# Alaska_1-1.net
KiCad netlist of a schematic drawn in Altium Designer
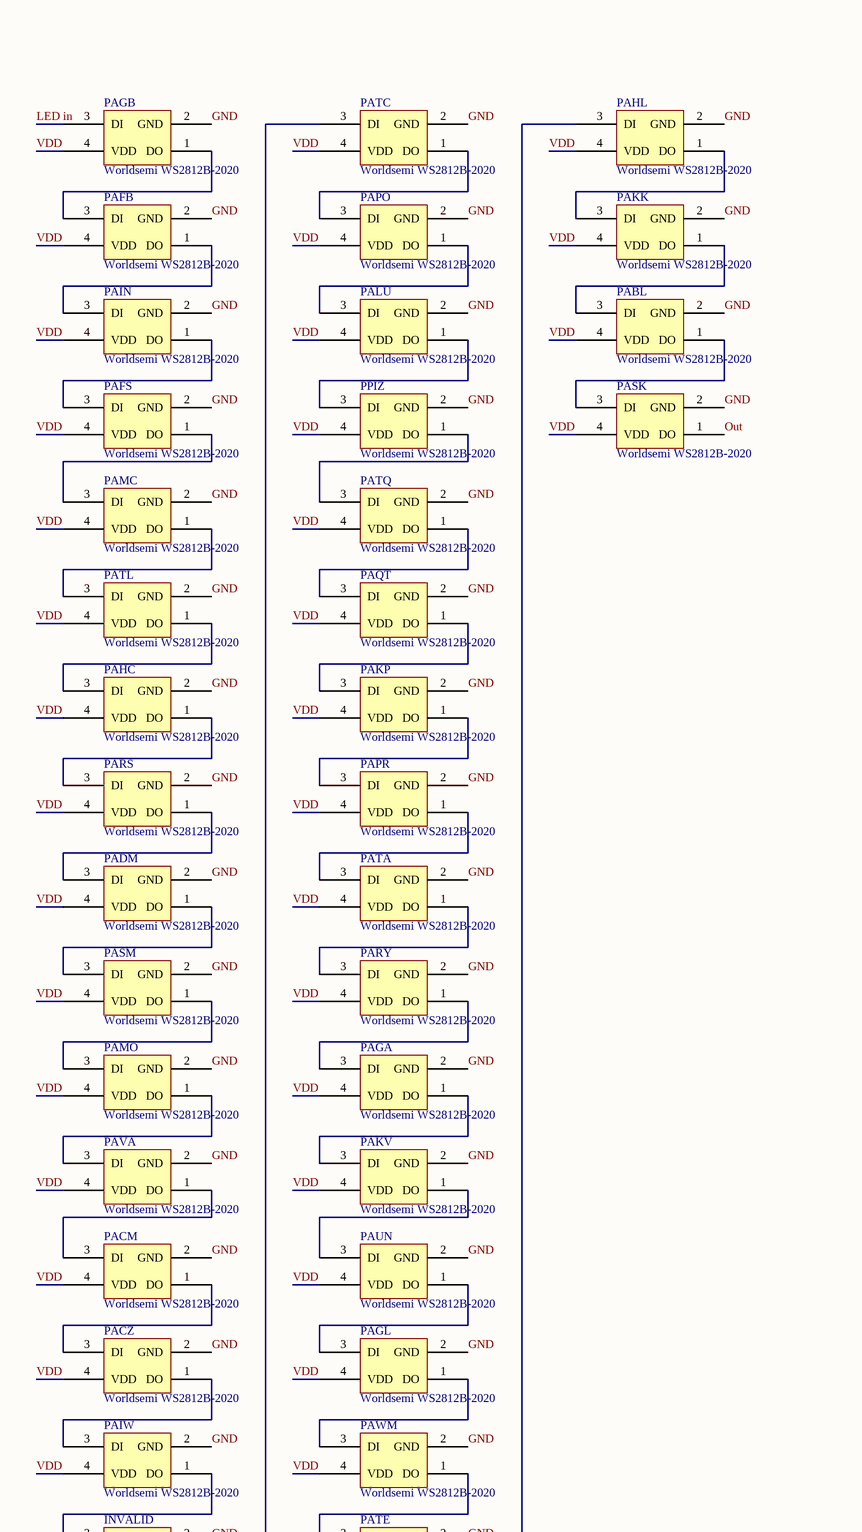
[diagram p0: Alaska 1-1.SchDoc, top left]
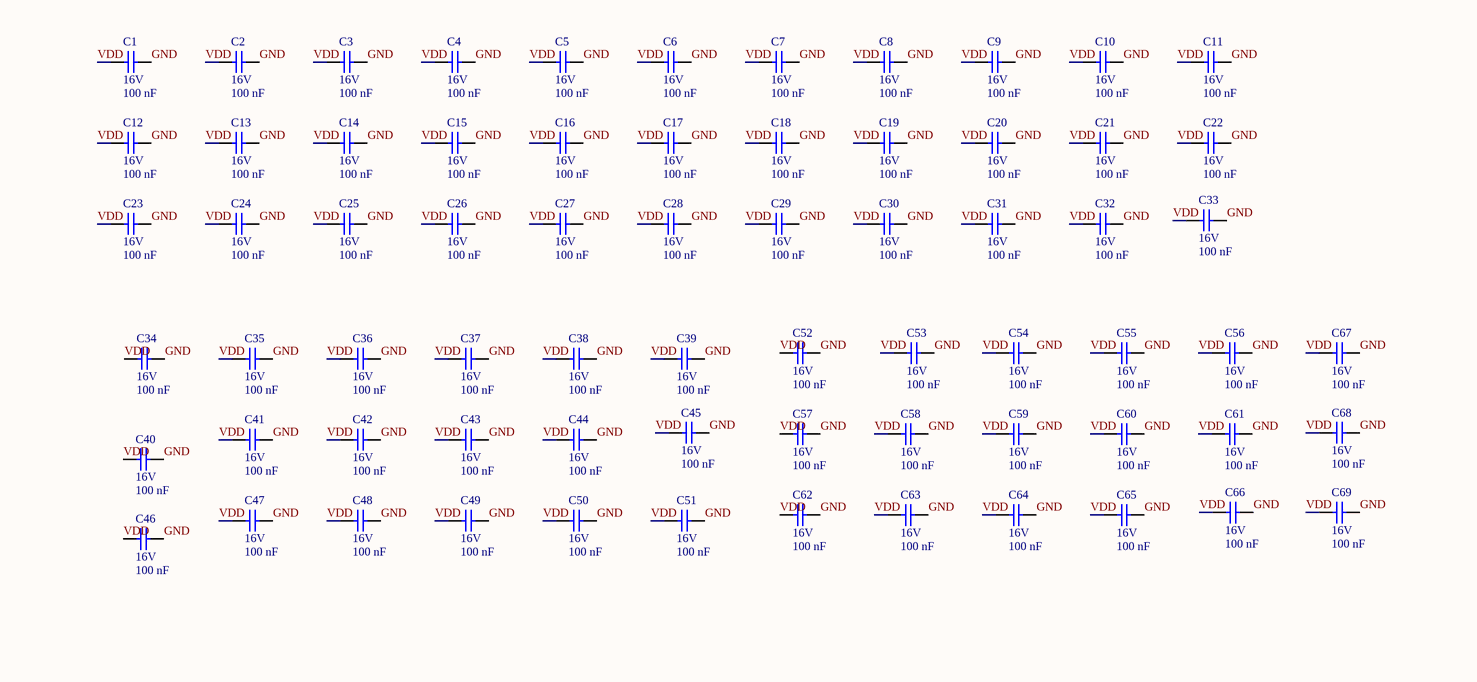
[diagram p1: Alaska 1-1.SchDoc, top middle]
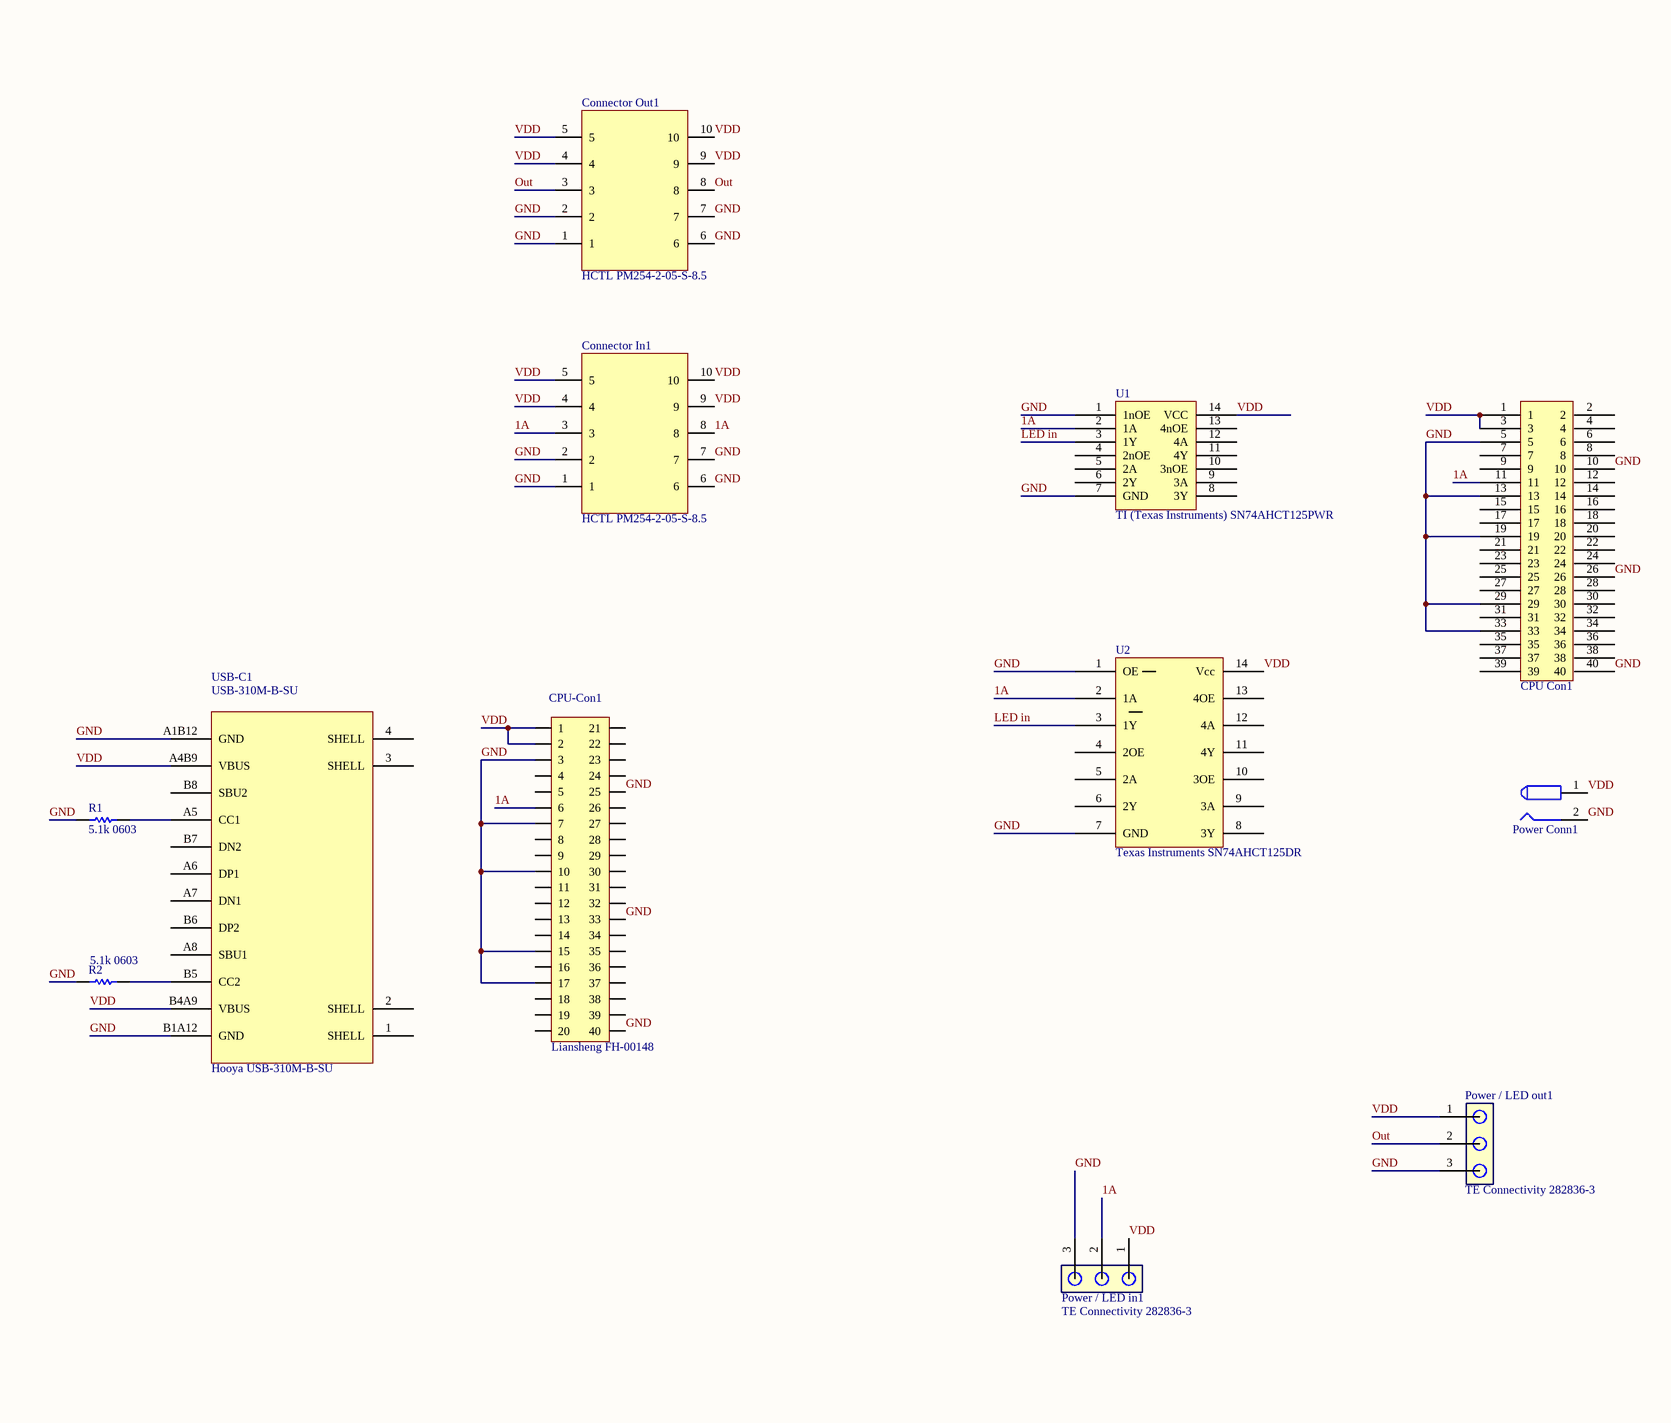
[diagram p2: Alaska 1-1.SchDoc, top right]
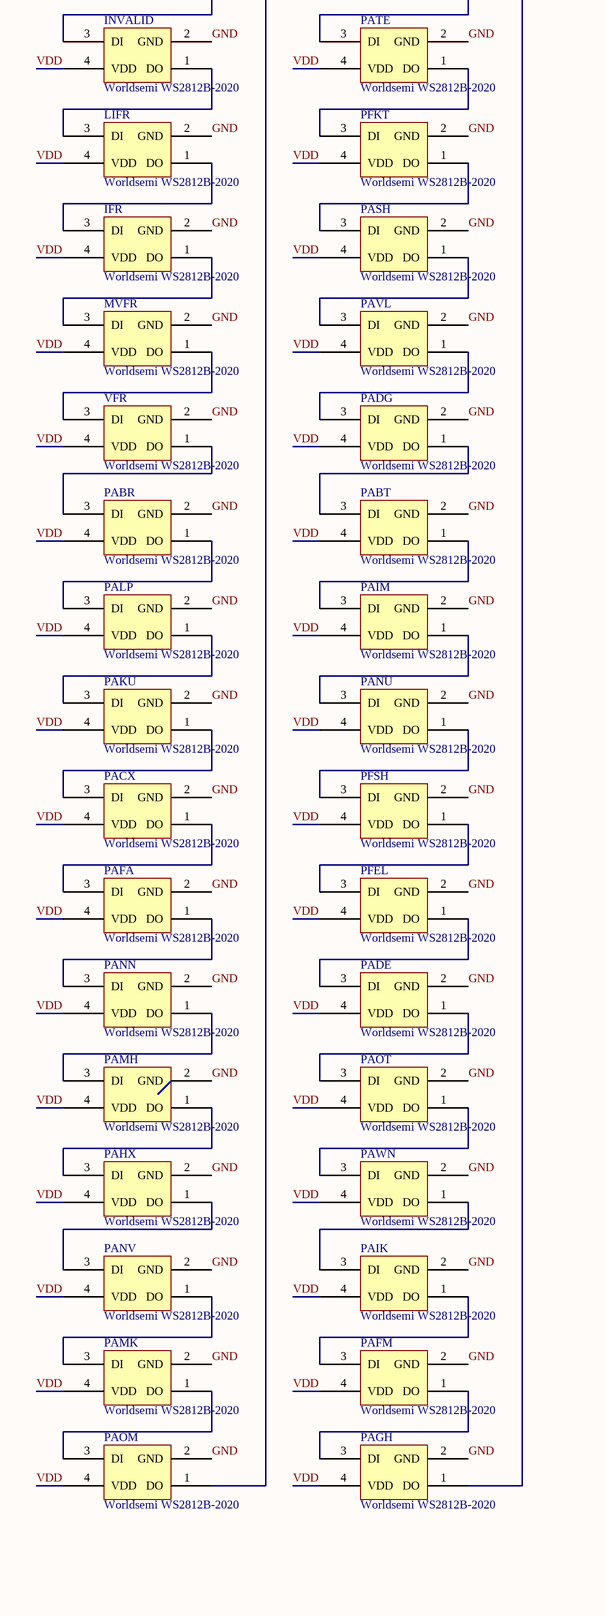
[diagram p3: Alaska 1-1.SchDoc, bottom left]
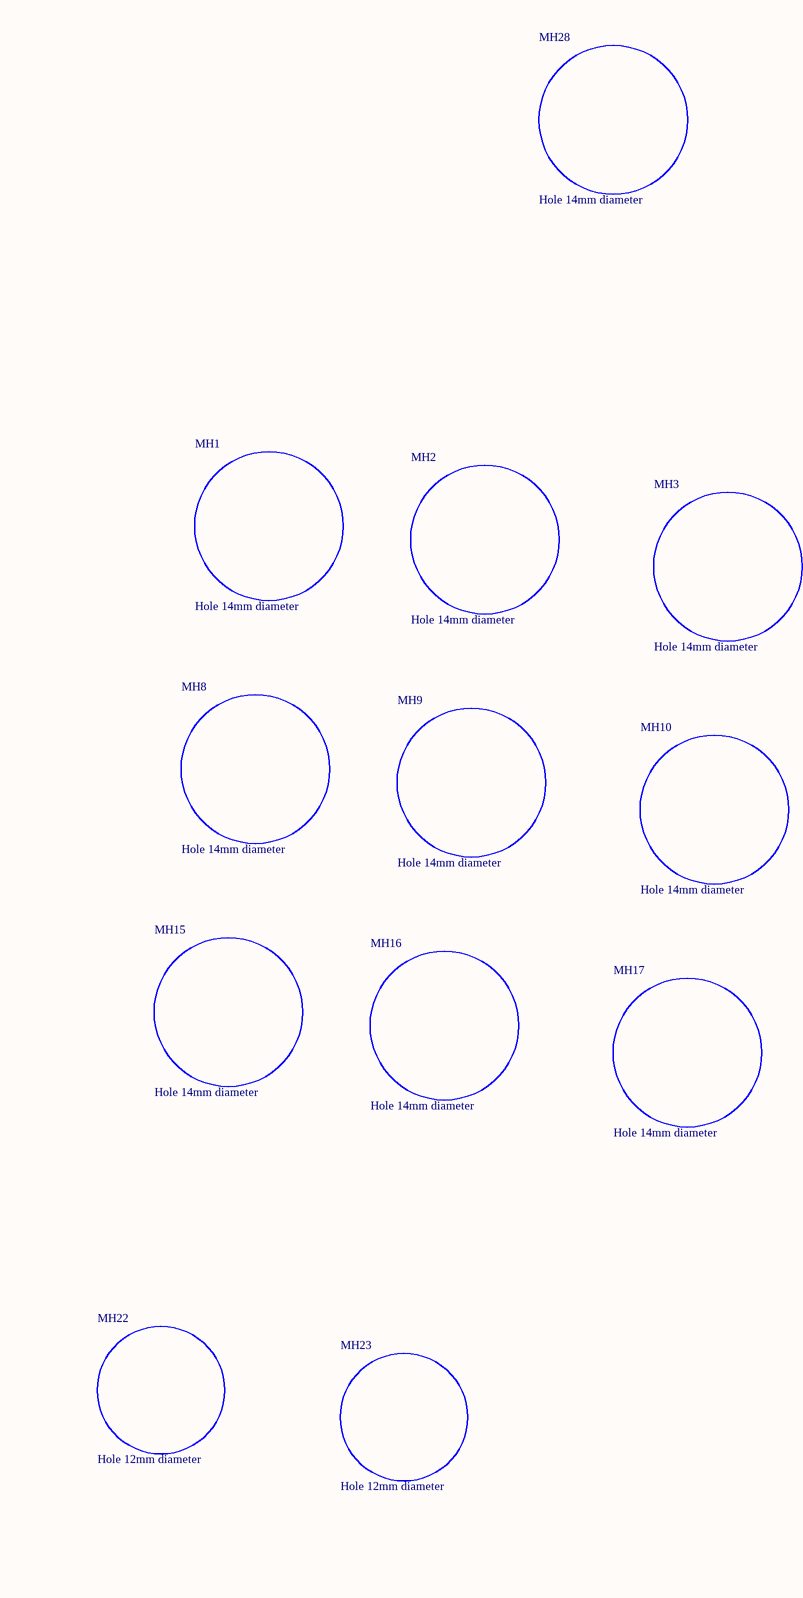
[diagram p4: Alaska 1-1.SchDoc, bottom middle]
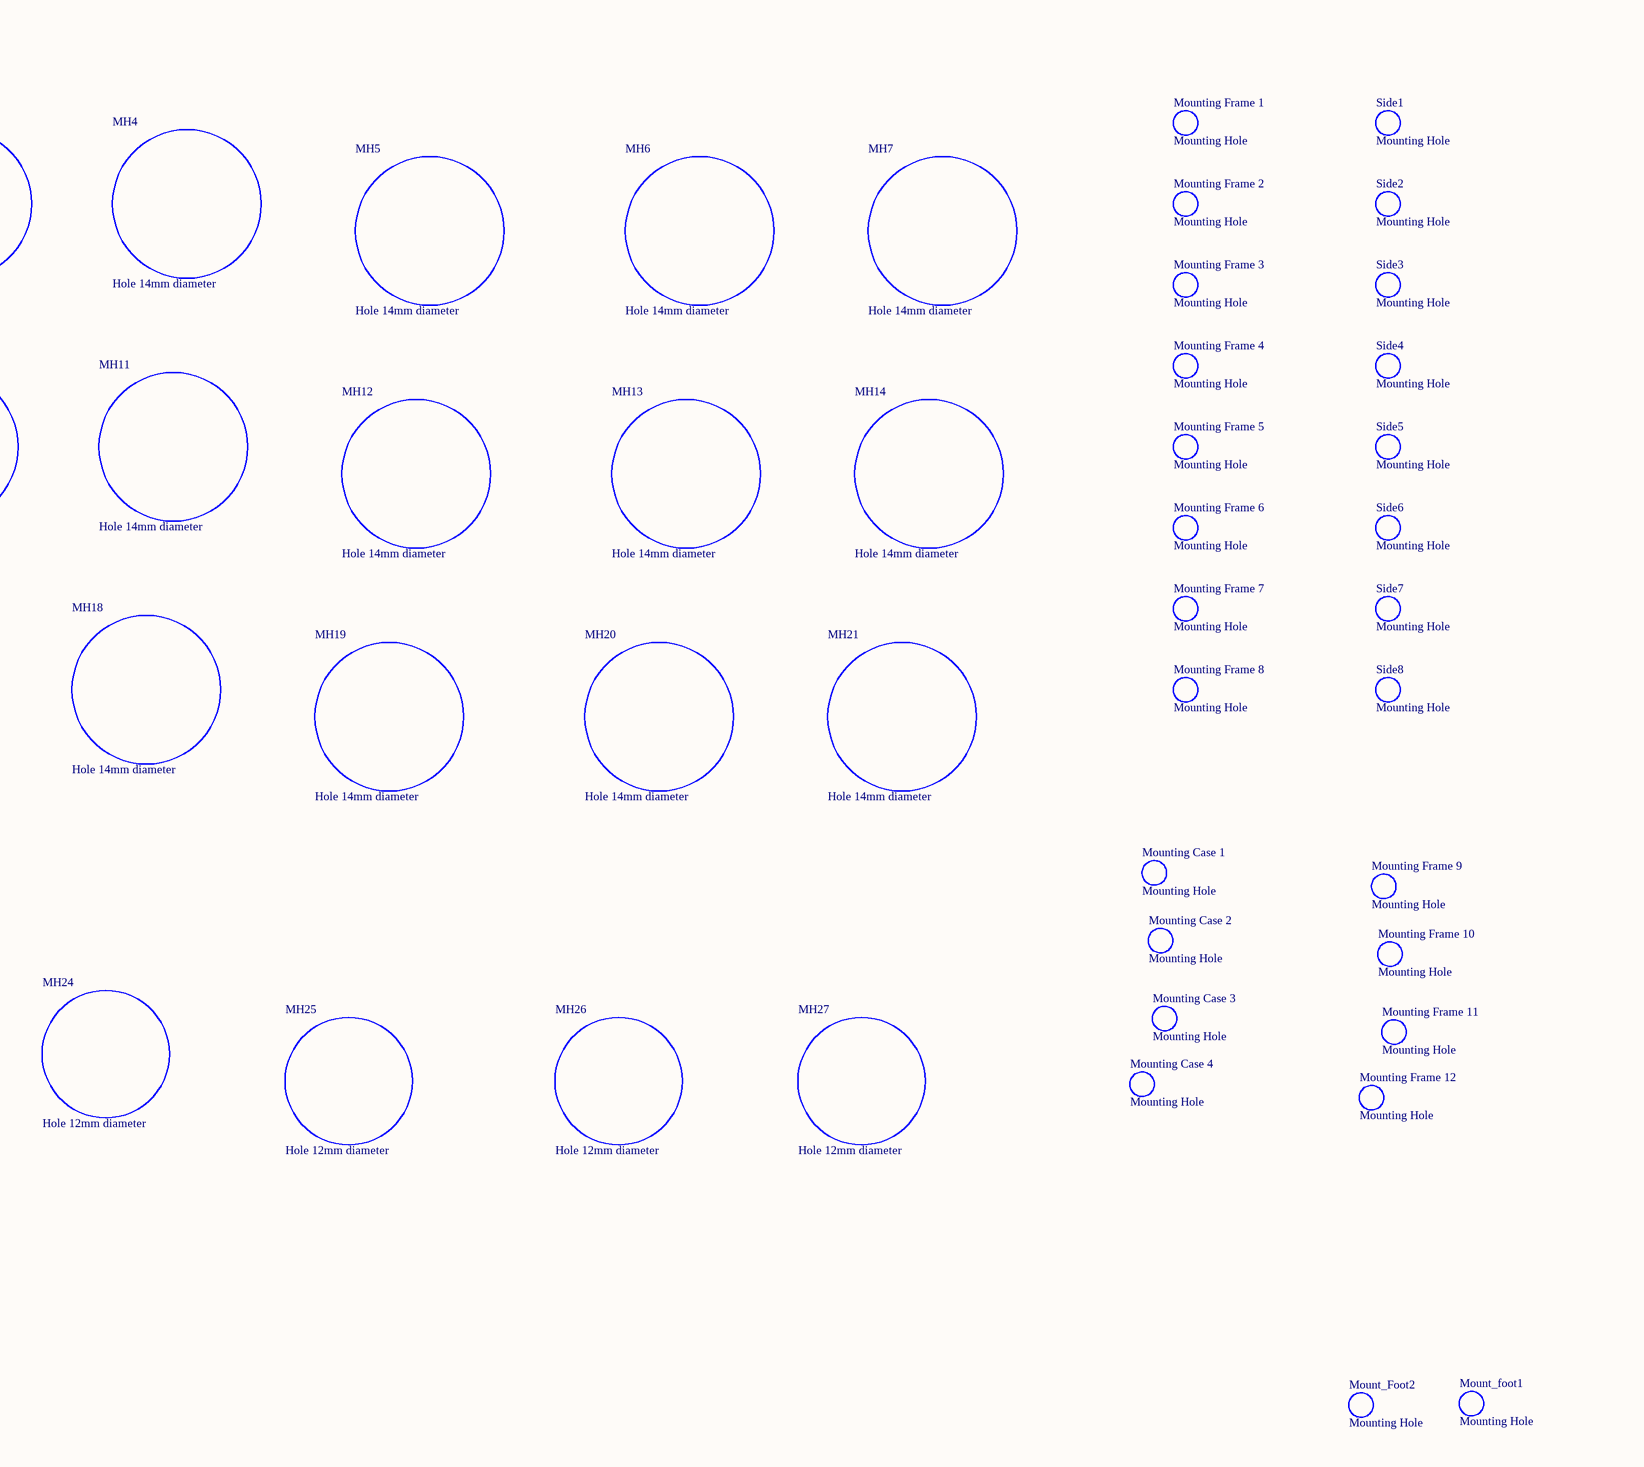
[diagram p5: Alaska 1-1.SchDoc, bottom right]

(export (version "E")
  (design (tool "Eeschema 10.0.6"))
  (components
    (comp (ref "C1")
      (value "16V")
      (footprint "CAPC1005X56X25NL10T15")
      (description "Generic CAP 0402, =Capacitance+','+Tolerance+','+Voltage+','+Dielectric+','+Case")
      (fields
        (field (name "CAPACITANCE") "100 nF")
        (field (name "MANUFACTURER PART NUMBER") "TBD")
        (field (name "VOLTAGE") "25V")
      )
      (libsource (lib "PCB_Project") (part "CMP-bf2276a55d9a60e5-20"))
    )
    (comp (ref "C2")
      (value "16V")
      (footprint "CAPC1005X56X25NL10T15")
      (description "Generic CAP 0402, =Capacitance+','+Tolerance+','+Voltage+','+Dielectric+','+Case")
      (fields
        (field (name "CAPACITANCE") "100 nF")
        (field (name "MANUFACTURER PART NUMBER") "TBD")
        (field (name "VOLTAGE") "25V")
      )
      (libsource (lib "PCB_Project") (part "CMP-bf2276a55d9a60e5-20"))
    )
    (comp (ref "C3")
      (value "16V")
      (footprint "CAPC1005X56X25NL10T15")
      (description "Generic CAP 0402, =Capacitance+','+Tolerance+','+Voltage+','+Dielectric+','+Case")
      (fields
        (field (name "CAPACITANCE") "100 nF")
        (field (name "MANUFACTURER PART NUMBER") "TBD")
        (field (name "VOLTAGE") "25V")
      )
      (libsource (lib "PCB_Project") (part "CMP-bf2276a55d9a60e5-20"))
    )
    (comp (ref "C4")
      (value "16V")
      (footprint "CAPC1005X56X25NL10T15")
      (description "Generic CAP 0402, =Capacitance+','+Tolerance+','+Voltage+','+Dielectric+','+Case")
      (fields
        (field (name "CAPACITANCE") "100 nF")
        (field (name "MANUFACTURER PART NUMBER") "TBD")
        (field (name "VOLTAGE") "25V")
      )
      (libsource (lib "PCB_Project") (part "CMP-bf2276a55d9a60e5-20"))
    )
    (comp (ref "C5")
      (value "16V")
      (footprint "CAPC1005X56X25NL10T15")
      (description "Generic CAP 0402, =Capacitance+','+Tolerance+','+Voltage+','+Dielectric+','+Case")
      (fields
        (field (name "CAPACITANCE") "100 nF")
        (field (name "MANUFACTURER PART NUMBER") "TBD")
        (field (name "VOLTAGE") "25V")
      )
      (libsource (lib "PCB_Project") (part "CMP-bf2276a55d9a60e5-20"))
    )
    (comp (ref "C6")
      (value "16V")
      (footprint "CAPC1005X56X25NL10T15")
      (description "Generic CAP 0402, =Capacitance+','+Tolerance+','+Voltage+','+Dielectric+','+Case")
      (fields
        (field (name "CAPACITANCE") "100 nF")
        (field (name "MANUFACTURER PART NUMBER") "TBD")
        (field (name "VOLTAGE") "25V")
      )
      (libsource (lib "PCB_Project") (part "CMP-bf2276a55d9a60e5-20"))
    )
    (comp (ref "C7")
      (value "16V")
      (footprint "CAPC1005X56X25NL10T15")
      (description "Generic CAP 0402, =Capacitance+','+Tolerance+','+Voltage+','+Dielectric+','+Case")
      (fields
        (field (name "CAPACITANCE") "100 nF")
        (field (name "MANUFACTURER PART NUMBER") "TBD")
        (field (name "VOLTAGE") "25V")
      )
      (libsource (lib "PCB_Project") (part "CMP-bf2276a55d9a60e5-20"))
    )
    (comp (ref "C8")
      (value "16V")
      (footprint "CAPC1005X56X25NL10T15")
      (description "Generic CAP 0402, =Capacitance+','+Tolerance+','+Voltage+','+Dielectric+','+Case")
      (fields
        (field (name "CAPACITANCE") "100 nF")
        (field (name "MANUFACTURER PART NUMBER") "TBD")
        (field (name "VOLTAGE") "25V")
      )
      (libsource (lib "PCB_Project") (part "CMP-bf2276a55d9a60e5-20"))
    )
    (comp (ref "C9")
      (value "16V")
      (footprint "CAPC1005X56X25NL10T15")
      (description "Generic CAP 0402, =Capacitance+','+Tolerance+','+Voltage+','+Dielectric+','+Case")
      (fields
        (field (name "CAPACITANCE") "100 nF")
        (field (name "MANUFACTURER PART NUMBER") "TBD")
        (field (name "VOLTAGE") "25V")
      )
      (libsource (lib "PCB_Project") (part "CMP-bf2276a55d9a60e5-20"))
    )
    (comp (ref "C10")
      (value "16V")
      (footprint "CAPC1005X56X25NL10T15")
      (description "Generic CAP 0402, =Capacitance+','+Tolerance+','+Voltage+','+Dielectric+','+Case")
      (fields
        (field (name "CAPACITANCE") "100 nF")
        (field (name "MANUFACTURER PART NUMBER") "TBD")
        (field (name "VOLTAGE") "25V")
      )
      (libsource (lib "PCB_Project") (part "CMP-bf2276a55d9a60e5-20"))
    )
    (comp (ref "C11")
      (value "16V")
      (footprint "CAPC1005X56X25NL10T15")
      (description "Generic CAP 0402, =Capacitance+','+Tolerance+','+Voltage+','+Dielectric+','+Case")
      (fields
        (field (name "CAPACITANCE") "100 nF")
        (field (name "MANUFACTURER PART NUMBER") "TBD")
        (field (name "VOLTAGE") "25V")
      )
      (libsource (lib "PCB_Project") (part "CMP-bf2276a55d9a60e5-20"))
    )
    (comp (ref "C12")
      (value "16V")
      (footprint "CAPC1005X56X25NL10T15")
      (description "Generic CAP 0402, =Capacitance+','+Tolerance+','+Voltage+','+Dielectric+','+Case")
      (fields
        (field (name "CAPACITANCE") "100 nF")
        (field (name "MANUFACTURER PART NUMBER") "TBD")
        (field (name "VOLTAGE") "25V")
      )
      (libsource (lib "PCB_Project") (part "CMP-bf2276a55d9a60e5-20"))
    )
    (comp (ref "C13")
      (value "16V")
      (footprint "CAPC1005X56X25NL10T15")
      (description "Generic CAP 0402, =Capacitance+','+Tolerance+','+Voltage+','+Dielectric+','+Case")
      (fields
        (field (name "CAPACITANCE") "100 nF")
        (field (name "MANUFACTURER PART NUMBER") "TBD")
        (field (name "VOLTAGE") "25V")
      )
      (libsource (lib "PCB_Project") (part "CMP-bf2276a55d9a60e5-20"))
    )
    (comp (ref "C14")
      (value "16V")
      (footprint "CAPC1005X56X25NL10T15")
      (description "Generic CAP 0402, =Capacitance+','+Tolerance+','+Voltage+','+Dielectric+','+Case")
      (fields
        (field (name "CAPACITANCE") "100 nF")
        (field (name "MANUFACTURER PART NUMBER") "TBD")
        (field (name "VOLTAGE") "25V")
      )
      (libsource (lib "PCB_Project") (part "CMP-bf2276a55d9a60e5-20"))
    )
    (comp (ref "C15")
      (value "16V")
      (footprint "CAPC1005X56X25NL10T15")
      (description "Generic CAP 0402, =Capacitance+','+Tolerance+','+Voltage+','+Dielectric+','+Case")
      (fields
        (field (name "CAPACITANCE") "100 nF")
        (field (name "MANUFACTURER PART NUMBER") "TBD")
        (field (name "VOLTAGE") "25V")
      )
      (libsource (lib "PCB_Project") (part "CMP-bf2276a55d9a60e5-20"))
    )
    (comp (ref "C16")
      (value "16V")
      (footprint "CAPC1005X56X25NL10T15")
      (description "Generic CAP 0402, =Capacitance+','+Tolerance+','+Voltage+','+Dielectric+','+Case")
      (fields
        (field (name "CAPACITANCE") "100 nF")
        (field (name "MANUFACTURER PART NUMBER") "TBD")
        (field (name "VOLTAGE") "25V")
      )
      (libsource (lib "PCB_Project") (part "CMP-bf2276a55d9a60e5-20"))
    )
    (comp (ref "C17")
      (value "16V")
      (footprint "CAPC1005X56X25NL10T15")
      (description "Generic CAP 0402, =Capacitance+','+Tolerance+','+Voltage+','+Dielectric+','+Case")
      (fields
        (field (name "CAPACITANCE") "100 nF")
        (field (name "MANUFACTURER PART NUMBER") "TBD")
        (field (name "VOLTAGE") "25V")
      )
      (libsource (lib "PCB_Project") (part "CMP-bf2276a55d9a60e5-20"))
    )
    (comp (ref "C18")
      (value "16V")
      (footprint "CAPC1005X56X25NL10T15")
      (description "Generic CAP 0402, =Capacitance+','+Tolerance+','+Voltage+','+Dielectric+','+Case")
      (fields
        (field (name "CAPACITANCE") "100 nF")
        (field (name "MANUFACTURER PART NUMBER") "TBD")
        (field (name "VOLTAGE") "25V")
      )
      (libsource (lib "PCB_Project") (part "CMP-bf2276a55d9a60e5-20"))
    )
    (comp (ref "C19")
      (value "16V")
      (footprint "CAPC1005X56X25NL10T15")
      (description "Generic CAP 0402, =Capacitance+','+Tolerance+','+Voltage+','+Dielectric+','+Case")
      (fields
        (field (name "CAPACITANCE") "100 nF")
        (field (name "MANUFACTURER PART NUMBER") "TBD")
        (field (name "VOLTAGE") "25V")
      )
      (libsource (lib "PCB_Project") (part "CMP-bf2276a55d9a60e5-20"))
    )
    (comp (ref "C20")
      (value "16V")
      (footprint "CAPC1005X56X25NL10T15")
      (description "Generic CAP 0402, =Capacitance+','+Tolerance+','+Voltage+','+Dielectric+','+Case")
      (fields
        (field (name "CAPACITANCE") "100 nF")
        (field (name "MANUFACTURER PART NUMBER") "TBD")
        (field (name "VOLTAGE") "25V")
      )
      (libsource (lib "PCB_Project") (part "CMP-bf2276a55d9a60e5-20"))
    )
    (comp (ref "C21")
      (value "16V")
      (footprint "CAPC1005X56X25NL10T15")
      (description "Generic CAP 0402, =Capacitance+','+Tolerance+','+Voltage+','+Dielectric+','+Case")
      (fields
        (field (name "CAPACITANCE") "100 nF")
        (field (name "MANUFACTURER PART NUMBER") "TBD")
        (field (name "VOLTAGE") "25V")
      )
      (libsource (lib "PCB_Project") (part "CMP-bf2276a55d9a60e5-20"))
    )
    (comp (ref "C22")
      (value "16V")
      (footprint "CAPC1005X56X25NL10T15")
      (description "Generic CAP 0402, =Capacitance+','+Tolerance+','+Voltage+','+Dielectric+','+Case")
      (fields
        (field (name "CAPACITANCE") "100 nF")
        (field (name "MANUFACTURER PART NUMBER") "TBD")
        (field (name "VOLTAGE") "25V")
      )
      (libsource (lib "PCB_Project") (part "CMP-bf2276a55d9a60e5-20"))
    )
    (comp (ref "C23")
      (value "16V")
      (footprint "CAPC1005X56X25NL10T15")
      (description "Generic CAP 0402, =Capacitance+','+Tolerance+','+Voltage+','+Dielectric+','+Case")
      (fields
        (field (name "CAPACITANCE") "100 nF")
        (field (name "MANUFACTURER PART NUMBER") "TBD")
        (field (name "VOLTAGE") "25V")
      )
      (libsource (lib "PCB_Project") (part "CMP-bf2276a55d9a60e5-20"))
    )
    (comp (ref "C24")
      (value "16V")
      (footprint "CAPC1005X56X25NL10T15")
      (description "Generic CAP 0402, =Capacitance+','+Tolerance+','+Voltage+','+Dielectric+','+Case")
      (fields
        (field (name "CAPACITANCE") "100 nF")
        (field (name "MANUFACTURER PART NUMBER") "TBD")
        (field (name "VOLTAGE") "25V")
      )
      (libsource (lib "PCB_Project") (part "CMP-bf2276a55d9a60e5-20"))
    )
    (comp (ref "C25")
      (value "16V")
      (footprint "CAPC1005X56X25NL10T15")
      (description "Generic CAP 0402, =Capacitance+','+Tolerance+','+Voltage+','+Dielectric+','+Case")
      (fields
        (field (name "CAPACITANCE") "100 nF")
        (field (name "MANUFACTURER PART NUMBER") "TBD")
        (field (name "VOLTAGE") "25V")
      )
      (libsource (lib "PCB_Project") (part "CMP-bf2276a55d9a60e5-20"))
    )
    (comp (ref "C26")
      (value "16V")
      (footprint "CAPC1005X56X25NL10T15")
      (description "Generic CAP 0402, =Capacitance+','+Tolerance+','+Voltage+','+Dielectric+','+Case")
      (fields
        (field (name "CAPACITANCE") "100 nF")
        (field (name "MANUFACTURER PART NUMBER") "TBD")
        (field (name "VOLTAGE") "25V")
      )
      (libsource (lib "PCB_Project") (part "CMP-bf2276a55d9a60e5-20"))
    )
    (comp (ref "C27")
      (value "16V")
      (footprint "CAPC1005X56X25NL10T15")
      (description "Generic CAP 0402, =Capacitance+','+Tolerance+','+Voltage+','+Dielectric+','+Case")
      (fields
        (field (name "CAPACITANCE") "100 nF")
        (field (name "MANUFACTURER PART NUMBER") "TBD")
        (field (name "VOLTAGE") "25V")
      )
      (libsource (lib "PCB_Project") (part "CMP-bf2276a55d9a60e5-20"))
    )
    (comp (ref "C28")
      (value "16V")
      (footprint "CAPC1005X56X25NL10T15")
      (description "Generic CAP 0402, =Capacitance+','+Tolerance+','+Voltage+','+Dielectric+','+Case")
      (fields
        (field (name "CAPACITANCE") "100 nF")
        (field (name "MANUFACTURER PART NUMBER") "TBD")
        (field (name "VOLTAGE") "25V")
      )
      (libsource (lib "PCB_Project") (part "CMP-bf2276a55d9a60e5-20"))
    )
    (comp (ref "C29")
      (value "16V")
      (footprint "CAPC1005X56X25NL10T15")
      (description "Generic CAP 0402, =Capacitance+','+Tolerance+','+Voltage+','+Dielectric+','+Case")
      (fields
        (field (name "CAPACITANCE") "100 nF")
        (field (name "MANUFACTURER PART NUMBER") "TBD")
        (field (name "VOLTAGE") "25V")
      )
      (libsource (lib "PCB_Project") (part "CMP-bf2276a55d9a60e5-20"))
    )
    (comp (ref "C30")
      (value "16V")
      (footprint "CAPC1005X56X25NL10T15")
      (description "Generic CAP 0402, =Capacitance+','+Tolerance+','+Voltage+','+Dielectric+','+Case")
      (fields
        (field (name "CAPACITANCE") "100 nF")
        (field (name "MANUFACTURER PART NUMBER") "TBD")
        (field (name "VOLTAGE") "25V")
      )
      (libsource (lib "PCB_Project") (part "CMP-bf2276a55d9a60e5-20"))
    )
    (comp (ref "C31")
      (value "16V")
      (footprint "CAPC1005X56X25NL10T15")
      (description "Generic CAP 0402, =Capacitance+','+Tolerance+','+Voltage+','+Dielectric+','+Case")
      (fields
        (field (name "CAPACITANCE") "100 nF")
        (field (name "MANUFACTURER PART NUMBER") "TBD")
        (field (name "VOLTAGE") "25V")
      )
      (libsource (lib "PCB_Project") (part "CMP-bf2276a55d9a60e5-20"))
    )
    (comp (ref "C32")
      (value "16V")
      (footprint "CAPC1005X56X25NL10T15")
      (description "Generic CAP 0402, =Capacitance+','+Tolerance+','+Voltage+','+Dielectric+','+Case")
      (fields
        (field (name "CAPACITANCE") "100 nF")
        (field (name "MANUFACTURER PART NUMBER") "TBD")
        (field (name "VOLTAGE") "25V")
      )
      (libsource (lib "PCB_Project") (part "CMP-bf2276a55d9a60e5-20"))
    )
    (comp (ref "C33")
      (value "16V")
      (footprint "CAPC1005X56X25NL10T15")
      (description "Generic CAP 0402, =Capacitance+','+Tolerance+','+Voltage+','+Dielectric+','+Case")
      (fields
        (field (name "CAPACITANCE") "100 nF")
        (field (name "MANUFACTURER PART NUMBER") "TBD")
        (field (name "VOLTAGE") "25V")
      )
      (libsource (lib "PCB_Project") (part "CMP-bf2276a55d9a60e5-20"))
    )
    (comp (ref "C34")
      (value "16V")
      (footprint "CAPC1005X56X25NL10T15")
      (description "Generic CAP 0402, =Capacitance+','+Tolerance+','+Voltage+','+Dielectric+','+Case")
      (fields
        (field (name "CAPACITANCE") "100 nF")
        (field (name "MANUFACTURER PART NUMBER") "TBD")
        (field (name "VOLTAGE") "25V")
      )
      (libsource (lib "PCB_Project") (part "CMP-bf2276a55d9a60e5-20"))
    )
    (comp (ref "C35")
      (value "16V")
      (footprint "CAPC1005X56X25NL10T15")
      (description "Generic CAP 0402, =Capacitance+','+Tolerance+','+Voltage+','+Dielectric+','+Case")
      (fields
        (field (name "CAPACITANCE") "100 nF")
        (field (name "MANUFACTURER PART NUMBER") "TBD")
        (field (name "VOLTAGE") "25V")
      )
      (libsource (lib "PCB_Project") (part "CMP-bf2276a55d9a60e5-20"))
    )
    (comp (ref "C36")
      (value "16V")
      (footprint "CAPC1005X56X25NL10T15")
      (description "Generic CAP 0402, =Capacitance+','+Tolerance+','+Voltage+','+Dielectric+','+Case")
      (fields
        (field (name "CAPACITANCE") "100 nF")
        (field (name "MANUFACTURER PART NUMBER") "TBD")
        (field (name "VOLTAGE") "25V")
      )
      (libsource (lib "PCB_Project") (part "CMP-bf2276a55d9a60e5-20"))
    )
    (comp (ref "C37")
      (value "16V")
      (footprint "CAPC1005X56X25NL10T15")
      (description "Generic CAP 0402, =Capacitance+','+Tolerance+','+Voltage+','+Dielectric+','+Case")
      (fields
        (field (name "CAPACITANCE") "100 nF")
        (field (name "MANUFACTURER PART NUMBER") "TBD")
        (field (name "VOLTAGE") "25V")
      )
      (libsource (lib "PCB_Project") (part "CMP-bf2276a55d9a60e5-20"))
    )
    (comp (ref "C38")
      (value "16V")
      (footprint "CAPC1005X56X25NL10T15")
      (description "Generic CAP 0402, =Capacitance+','+Tolerance+','+Voltage+','+Dielectric+','+Case")
      (fields
        (field (name "CAPACITANCE") "100 nF")
        (field (name "MANUFACTURER PART NUMBER") "TBD")
        (field (name "VOLTAGE") "25V")
      )
      (libsource (lib "PCB_Project") (part "CMP-bf2276a55d9a60e5-20"))
    )
    (comp (ref "C39")
      (value "16V")
      (footprint "CAPC1005X56X25NL10T15")
      (description "Generic CAP 0402, =Capacitance+','+Tolerance+','+Voltage+','+Dielectric+','+Case")
      (fields
        (field (name "CAPACITANCE") "100 nF")
        (field (name "MANUFACTURER PART NUMBER") "TBD")
        (field (name "VOLTAGE") "25V")
      )
      (libsource (lib "PCB_Project") (part "CMP-bf2276a55d9a60e5-20"))
    )
    (comp (ref "C40")
      (value "16V")
      (footprint "CAPC1005X56X25NL10T15")
      (description "Generic CAP 0402, =Capacitance+','+Tolerance+','+Voltage+','+Dielectric+','+Case")
      (fields
        (field (name "CAPACITANCE") "100 nF")
        (field (name "MANUFACTURER PART NUMBER") "TBD")
        (field (name "VOLTAGE") "25V")
      )
      (libsource (lib "PCB_Project") (part "CMP-bf2276a55d9a60e5-20"))
    )
    (comp (ref "C41")
      (value "16V")
      (footprint "CAPC1005X56X25NL10T15")
      (description "Generic CAP 0402, =Capacitance+','+Tolerance+','+Voltage+','+Dielectric+','+Case")
      (fields
        (field (name "CAPACITANCE") "100 nF")
        (field (name "MANUFACTURER PART NUMBER") "TBD")
        (field (name "VOLTAGE") "25V")
      )
      (libsource (lib "PCB_Project") (part "CMP-bf2276a55d9a60e5-20"))
    )
    (comp (ref "C42")
      (value "16V")
      (footprint "CAPC1005X56X25NL10T15")
      (description "Generic CAP 0402, =Capacitance+','+Tolerance+','+Voltage+','+Dielectric+','+Case")
      (fields
        (field (name "CAPACITANCE") "100 nF")
        (field (name "MANUFACTURER PART NUMBER") "TBD")
        (field (name "VOLTAGE") "25V")
      )
      (libsource (lib "PCB_Project") (part "CMP-bf2276a55d9a60e5-20"))
    )
    (comp (ref "C43")
      (value "16V")
      (footprint "CAPC1005X56X25NL10T15")
      (description "Generic CAP 0402, =Capacitance+','+Tolerance+','+Voltage+','+Dielectric+','+Case")
      (fields
        (field (name "CAPACITANCE") "100 nF")
        (field (name "MANUFACTURER PART NUMBER") "TBD")
        (field (name "VOLTAGE") "25V")
      )
      (libsource (lib "PCB_Project") (part "CMP-bf2276a55d9a60e5-20"))
    )
    (comp (ref "C44")
      (value "16V")
      (footprint "CAPC1005X56X25NL10T15")
      (description "Generic CAP 0402, =Capacitance+','+Tolerance+','+Voltage+','+Dielectric+','+Case")
      (fields
        (field (name "CAPACITANCE") "100 nF")
        (field (name "MANUFACTURER PART NUMBER") "TBD")
        (field (name "VOLTAGE") "25V")
      )
      (libsource (lib "PCB_Project") (part "CMP-bf2276a55d9a60e5-20"))
    )
    (comp (ref "C45")
      (value "16V")
      (footprint "CAPC1005X56X25NL10T15")
      (description "Generic CAP 0402, =Capacitance+','+Tolerance+','+Voltage+','+Dielectric+','+Case")
      (fields
        (field (name "CAPACITANCE") "100 nF")
        (field (name "MANUFACTURER PART NUMBER") "TBD")
        (field (name "VOLTAGE") "25V")
      )
      (libsource (lib "PCB_Project") (part "CMP-bf2276a55d9a60e5-20"))
    )
    (comp (ref "C46")
      (value "16V")
      (footprint "CAPC1005X56X25NL10T15")
      (description "Generic CAP 0402, =Capacitance+','+Tolerance+','+Voltage+','+Dielectric+','+Case")
      (fields
        (field (name "CAPACITANCE") "100 nF")
        (field (name "MANUFACTURER PART NUMBER") "TBD")
        (field (name "VOLTAGE") "25V")
      )
      (libsource (lib "PCB_Project") (part "CMP-bf2276a55d9a60e5-20"))
    )
    (comp (ref "C47")
      (value "16V")
      (footprint "CAPC1005X56X25NL10T15")
      (description "Generic CAP 0402, =Capacitance+','+Tolerance+','+Voltage+','+Dielectric+','+Case")
      (fields
        (field (name "CAPACITANCE") "100 nF")
        (field (name "MANUFACTURER PART NUMBER") "TBD")
        (field (name "VOLTAGE") "25V")
      )
      (libsource (lib "PCB_Project") (part "CMP-bf2276a55d9a60e5-20"))
    )
    (comp (ref "C48")
      (value "16V")
      (footprint "CAPC1005X56X25NL10T15")
      (description "Generic CAP 0402, =Capacitance+','+Tolerance+','+Voltage+','+Dielectric+','+Case")
      (fields
        (field (name "CAPACITANCE") "100 nF")
        (field (name "MANUFACTURER PART NUMBER") "TBD")
        (field (name "VOLTAGE") "25V")
      )
      (libsource (lib "PCB_Project") (part "CMP-bf2276a55d9a60e5-20"))
    )
    (comp (ref "C49")
      (value "16V")
      (footprint "CAPC1005X56X25NL10T15")
      (description "Generic CAP 0402, =Capacitance+','+Tolerance+','+Voltage+','+Dielectric+','+Case")
      (fields
        (field (name "CAPACITANCE") "100 nF")
        (field (name "MANUFACTURER PART NUMBER") "TBD")
        (field (name "VOLTAGE") "25V")
      )
      (libsource (lib "PCB_Project") (part "CMP-bf2276a55d9a60e5-20"))
    )
    (comp (ref "C50")
      (value "16V")
      (footprint "CAPC1005X56X25NL10T15")
      (description "Generic CAP 0402, =Capacitance+','+Tolerance+','+Voltage+','+Dielectric+','+Case")
      (fields
        (field (name "CAPACITANCE") "100 nF")
        (field (name "MANUFACTURER PART NUMBER") "TBD")
        (field (name "VOLTAGE") "25V")
      )
      (libsource (lib "PCB_Project") (part "CMP-bf2276a55d9a60e5-20"))
    )
    (comp (ref "C51")
      (value "16V")
      (footprint "CAPC1005X56X25NL10T15")
      (description "Generic CAP 0402, =Capacitance+','+Tolerance+','+Voltage+','+Dielectric+','+Case")
      (fields
        (field (name "CAPACITANCE") "100 nF")
        (field (name "MANUFACTURER PART NUMBER") "TBD")
        (field (name "VOLTAGE") "25V")
      )
      (libsource (lib "PCB_Project") (part "CMP-bf2276a55d9a60e5-20"))
    )
    (comp (ref "C52")
      (value "16V")
      (footprint "CAPC1005X56X25NL10T15")
      (description "Generic CAP 0402, =Capacitance+','+Tolerance+','+Voltage+','+Dielectric+','+Case")
      (fields
        (field (name "CAPACITANCE") "100 nF")
        (field (name "MANUFACTURER PART NUMBER") "TBD")
        (field (name "VOLTAGE") "25V")
      )
      (libsource (lib "PCB_Project") (part "CMP-bf2276a55d9a60e5-20"))
    )
    (comp (ref "C53")
      (value "16V")
      (footprint "CAPC1005X56X25NL10T15")
      (description "Generic CAP 0402, =Capacitance+','+Tolerance+','+Voltage+','+Dielectric+','+Case")
      (fields
        (field (name "CAPACITANCE") "100 nF")
        (field (name "MANUFACTURER PART NUMBER") "TBD")
        (field (name "VOLTAGE") "25V")
      )
      (libsource (lib "PCB_Project") (part "CMP-bf2276a55d9a60e5-20"))
    )
    (comp (ref "C54")
      (value "16V")
      (footprint "CAPC1005X56X25NL10T15")
      (description "Generic CAP 0402, =Capacitance+','+Tolerance+','+Voltage+','+Dielectric+','+Case")
      (fields
        (field (name "CAPACITANCE") "100 nF")
        (field (name "MANUFACTURER PART NUMBER") "TBD")
        (field (name "VOLTAGE") "25V")
      )
      (libsource (lib "PCB_Project") (part "CMP-bf2276a55d9a60e5-20"))
    )
    (comp (ref "C55")
      (value "16V")
      (footprint "CAPC1005X56X25NL10T15")
      (description "Generic CAP 0402, =Capacitance+','+Tolerance+','+Voltage+','+Dielectric+','+Case")
      (fields
        (field (name "CAPACITANCE") "100 nF")
        (field (name "MANUFACTURER PART NUMBER") "TBD")
        (field (name "VOLTAGE") "25V")
      )
      (libsource (lib "PCB_Project") (part "CMP-bf2276a55d9a60e5-20"))
    )
    (comp (ref "C56")
      (value "16V")
      (footprint "CAPC1005X56X25NL10T15")
      (description "Generic CAP 0402, =Capacitance+','+Tolerance+','+Voltage+','+Dielectric+','+Case")
      (fields
        (field (name "CAPACITANCE") "100 nF")
        (field (name "MANUFACTURER PART NUMBER") "TBD")
        (field (name "VOLTAGE") "25V")
      )
      (libsource (lib "PCB_Project") (part "CMP-bf2276a55d9a60e5-20"))
    )
    (comp (ref "C57")
      (value "16V")
      (footprint "CAPC1005X56X25NL10T15")
      (description "Generic CAP 0402, =Capacitance+','+Tolerance+','+Voltage+','+Dielectric+','+Case")
      (fields
        (field (name "CAPACITANCE") "100 nF")
        (field (name "MANUFACTURER PART NUMBER") "TBD")
        (field (name "VOLTAGE") "25V")
      )
      (libsource (lib "PCB_Project") (part "CMP-bf2276a55d9a60e5-20"))
    )
    (comp (ref "C58")
      (value "16V")
      (footprint "CAPC1005X56X25NL10T15")
      (description "Generic CAP 0402, =Capacitance+','+Tolerance+','+Voltage+','+Dielectric+','+Case")
      (fields
        (field (name "CAPACITANCE") "100 nF")
        (field (name "MANUFACTURER PART NUMBER") "TBD")
        (field (name "VOLTAGE") "25V")
      )
      (libsource (lib "PCB_Project") (part "CMP-bf2276a55d9a60e5-20"))
    )
    (comp (ref "C59")
      (value "16V")
      (footprint "CAPC1005X56X25NL10T15")
      (description "Generic CAP 0402, =Capacitance+','+Tolerance+','+Voltage+','+Dielectric+','+Case")
      (fields
        (field (name "CAPACITANCE") "100 nF")
        (field (name "MANUFACTURER PART NUMBER") "TBD")
        (field (name "VOLTAGE") "25V")
      )
      (libsource (lib "PCB_Project") (part "CMP-bf2276a55d9a60e5-20"))
    )
    (comp (ref "C60")
      (value "16V")
      (footprint "CAPC1005X56X25NL10T15")
      (description "Generic CAP 0402, =Capacitance+','+Tolerance+','+Voltage+','+Dielectric+','+Case")
      (fields
        (field (name "CAPACITANCE") "100 nF")
        (field (name "MANUFACTURER PART NUMBER") "TBD")
        (field (name "VOLTAGE") "25V")
      )
      (libsource (lib "PCB_Project") (part "CMP-bf2276a55d9a60e5-20"))
    )
    (comp (ref "C61")
      (value "16V")
      (footprint "CAPC1005X56X25NL10T15")
      (description "Generic CAP 0402, =Capacitance+','+Tolerance+','+Voltage+','+Dielectric+','+Case")
      (fields
        (field (name "CAPACITANCE") "100 nF")
        (field (name "MANUFACTURER PART NUMBER") "TBD")
        (field (name "VOLTAGE") "25V")
      )
      (libsource (lib "PCB_Project") (part "CMP-bf2276a55d9a60e5-20"))
    )
    (comp (ref "C62")
      (value "16V")
      (footprint "CAPC1005X56X25NL10T15")
      (description "Generic CAP 0402, =Capacitance+','+Tolerance+','+Voltage+','+Dielectric+','+Case")
      (fields
        (field (name "CAPACITANCE") "100 nF")
        (field (name "MANUFACTURER PART NUMBER") "TBD")
        (field (name "VOLTAGE") "25V")
      )
      (libsource (lib "PCB_Project") (part "CMP-bf2276a55d9a60e5-20"))
    )
    (comp (ref "C63")
      (value "16V")
      (footprint "CAPC1005X56X25NL10T15")
      (description "Generic CAP 0402, =Capacitance+','+Tolerance+','+Voltage+','+Dielectric+','+Case")
      (fields
        (field (name "CAPACITANCE") "100 nF")
        (field (name "MANUFACTURER PART NUMBER") "TBD")
        (field (name "VOLTAGE") "25V")
      )
      (libsource (lib "PCB_Project") (part "CMP-bf2276a55d9a60e5-20"))
    )
    (comp (ref "C64")
      (value "16V")
      (footprint "CAPC1005X56X25NL10T15")
      (description "Generic CAP 0402, =Capacitance+','+Tolerance+','+Voltage+','+Dielectric+','+Case")
      (fields
        (field (name "CAPACITANCE") "100 nF")
        (field (name "MANUFACTURER PART NUMBER") "TBD")
        (field (name "VOLTAGE") "25V")
      )
      (libsource (lib "PCB_Project") (part "CMP-bf2276a55d9a60e5-20"))
    )
    (comp (ref "C65")
      (value "16V")
      (footprint "CAPC1005X56X25NL10T15")
      (description "Generic CAP 0402, =Capacitance+','+Tolerance+','+Voltage+','+Dielectric+','+Case")
      (fields
        (field (name "CAPACITANCE") "100 nF")
        (field (name "MANUFACTURER PART NUMBER") "TBD")
        (field (name "VOLTAGE") "25V")
      )
      (libsource (lib "PCB_Project") (part "CMP-bf2276a55d9a60e5-20"))
    )
    (comp (ref "C66")
      (value "16V")
      (footprint "CAPC1005X56X25NL10T15")
      (description "Generic CAP 0402, =Capacitance+','+Tolerance+','+Voltage+','+Dielectric+','+Case")
      (fields
        (field (name "CAPACITANCE") "100 nF")
        (field (name "MANUFACTURER PART NUMBER") "TBD")
        (field (name "VOLTAGE") "25V")
      )
      (libsource (lib "PCB_Project") (part "CMP-bf2276a55d9a60e5-20"))
    )
    (comp (ref "C67")
      (value "16V")
      (footprint "CAPC1005X56X25NL10T15")
      (description "Generic CAP 0402, =Capacitance+','+Tolerance+','+Voltage+','+Dielectric+','+Case")
      (fields
        (field (name "CAPACITANCE") "100 nF")
        (field (name "MANUFACTURER PART NUMBER") "TBD")
        (field (name "VOLTAGE") "25V")
      )
      (libsource (lib "PCB_Project") (part "CMP-bf2276a55d9a60e5-20"))
    )
    (comp (ref "C68")
      (value "16V")
      (footprint "CAPC1005X56X25NL10T15")
      (description "Generic CAP 0402, =Capacitance+','+Tolerance+','+Voltage+','+Dielectric+','+Case")
      (fields
        (field (name "CAPACITANCE") "100 nF")
        (field (name "MANUFACTURER PART NUMBER") "TBD")
        (field (name "VOLTAGE") "25V")
      )
      (libsource (lib "PCB_Project") (part "CMP-bf2276a55d9a60e5-20"))
    )
    (comp (ref "C69")
      (value "16V")
      (footprint "CAPC1005X56X25NL10T15")
      (description "Generic CAP 0402, =Capacitance+','+Tolerance+','+Voltage+','+Dielectric+','+Case")
      (fields
        (field (name "CAPACITANCE") "100 nF")
        (field (name "MANUFACTURER PART NUMBER") "TBD")
        (field (name "VOLTAGE") "25V")
      )
      (libsource (lib "PCB_Project") (part "CMP-bf2276a55d9a60e5-20"))
    )
    (comp (ref "Connector In1")
      (value "HCTL PM254-2-05-S-8.5")
      (footprint "PM254-2-05-S-8.5")
      (libsource (lib "PilotMap_Main_Parts") (part "PM254-2-05-S-8.5"))
    )
    (comp (ref "Connector Out1")
      (value "HCTL PM254-2-05-S-8.5")
      (footprint "PM254-2-05-S-8.5")
      (libsource (lib "PilotMap_Main_Parts") (part "PM254-2-05-S-8.5"))
    )
    (comp (ref "CPU Con1")
      (value "40 pin Female connector")
      (footprint "Harwin 40 pin Female")
      (description "2.54mm (0.1\") Pitch DIL Vertical PC Tail Socket Assembly, tin, 20+20 contacts")
      (libsource (lib "PCB_Project") (part "CMP-2482621-16"))
    )
    (comp (ref "CPU-Con1")
      (value "Liansheng FH-00148")
      (footprint "Liansheng_FH-00148_Footprint_01")
      (libsource (lib "PCB_Project") (part "CMP-xf5hfsu41fuj64nwsg7i-2"))
    )
    (comp (ref "IFR")
      (value "Worldsemi WS2812B-2020")
      (footprint "PCB-18681qzhn4j348g96a9l-1")
      (fields (field (name "MANUFACTURER PART NUMBER") "WS2812B-2020"))
      (libsource (lib "PCB_Project") (part "CMP-30b1feb25fa9ef76-6"))
    )
    (comp (ref "INVALID")
      (value "Worldsemi WS2812B-2020")
      (footprint "PCB-18681qzhn4j348g96a9l-1")
      (fields (field (name "MANUFACTURER PART NUMBER") "WS2812B-2020"))
      (libsource (lib "PCB_Project") (part "CMP-30b1feb25fa9ef76-6"))
    )
    (comp (ref "LIFR")
      (value "Worldsemi WS2812B-2020")
      (footprint "PCB-18681qzhn4j348g96a9l-1")
      (fields (field (name "MANUFACTURER PART NUMBER") "WS2812B-2020"))
      (libsource (lib "PCB_Project") (part "CMP-30b1feb25fa9ef76-6"))
    )
    (comp (ref "MH1")
      (value "Hole 14mm diameter")
      (footprint "Mounting Hole 14mm")
      (description "Hole for mounting")
      (libsource (lib "PilotMap_Main_Parts") (part "Mounting Hole 14mm"))
    )
    (comp (ref "MH2")
      (value "Hole 14mm diameter")
      (footprint "Mounting Hole 14mm")
      (description "Hole for mounting")
      (libsource (lib "PilotMap_Main_Parts") (part "Mounting Hole 14mm"))
    )
    (comp (ref "MH3")
      (value "Hole 14mm diameter")
      (footprint "Mounting Hole 14mm")
      (description "Hole for mounting")
      (libsource (lib "PilotMap_Main_Parts") (part "Mounting Hole 14mm"))
    )
    (comp (ref "MH4")
      (value "Hole 14mm diameter")
      (footprint "Mounting Hole 14mm")
      (description "Hole for mounting")
      (libsource (lib "PilotMap_Main_Parts") (part "Mounting Hole 14mm"))
    )
    (comp (ref "MH5")
      (value "Hole 14mm diameter")
      (footprint "Mounting Hole 14mm")
      (description "Hole for mounting")
      (libsource (lib "PilotMap_Main_Parts") (part "Mounting Hole 14mm"))
    )
    (comp (ref "MH6")
      (value "Hole 14mm diameter")
      (footprint "Mounting Hole 14mm")
      (description "Hole for mounting")
      (libsource (lib "PilotMap_Main_Parts") (part "Mounting Hole 14mm"))
    )
    (comp (ref "MH7")
      (value "Hole 14mm diameter")
      (footprint "Mounting Hole 14mm")
      (description "Hole for mounting")
      (libsource (lib "PilotMap_Main_Parts") (part "Mounting Hole 14mm"))
    )
    (comp (ref "MH8")
      (value "Hole 14mm diameter")
      (footprint "Mounting Hole 14mm")
      (description "Hole for mounting")
      (libsource (lib "PilotMap_Main_Parts") (part "Mounting Hole 14mm"))
    )
    (comp (ref "MH9")
      (value "Hole 14mm diameter")
      (footprint "Mounting Hole 14mm")
      (description "Hole for mounting")
      (libsource (lib "PilotMap_Main_Parts") (part "Mounting Hole 14mm"))
    )
    (comp (ref "MH10")
      (value "Hole 14mm diameter")
      (footprint "Mounting Hole 14mm")
      (description "Hole for mounting")
      (libsource (lib "PilotMap_Main_Parts") (part "Mounting Hole 14mm"))
    )
    (comp (ref "MH11")
      (value "Hole 14mm diameter")
      (footprint "Mounting Hole 14mm")
      (description "Hole for mounting")
      (libsource (lib "PilotMap_Main_Parts") (part "Mounting Hole 14mm"))
    )
    (comp (ref "MH12")
      (value "Hole 14mm diameter")
      (footprint "Mounting Hole 14mm")
      (description "Hole for mounting")
      (libsource (lib "PilotMap_Main_Parts") (part "Mounting Hole 14mm"))
    )
    (comp (ref "MH13")
      (value "Hole 14mm diameter")
      (footprint "Mounting Hole 14mm")
      (description "Hole for mounting")
      (libsource (lib "PilotMap_Main_Parts") (part "Mounting Hole 14mm"))
    )
    (comp (ref "MH14")
      (value "Hole 14mm diameter")
      (footprint "Mounting Hole 14mm")
      (description "Hole for mounting")
      (libsource (lib "PilotMap_Main_Parts") (part "Mounting Hole 14mm"))
    )
    (comp (ref "MH15")
      (value "Hole 14mm diameter")
      (footprint "Mounting Hole 14mm")
      (description "Hole for mounting")
      (libsource (lib "PilotMap_Main_Parts") (part "Mounting Hole 14mm"))
    )
    (comp (ref "MH16")
      (value "Hole 14mm diameter")
      (footprint "Mounting Hole 14mm")
      (description "Hole for mounting")
      (libsource (lib "PilotMap_Main_Parts") (part "Mounting Hole 14mm"))
    )
    (comp (ref "MH17")
      (value "Hole 14mm diameter")
      (footprint "Mounting Hole 14mm")
      (description "Hole for mounting")
      (libsource (lib "PilotMap_Main_Parts") (part "Mounting Hole 14mm"))
    )
    (comp (ref "MH18")
      (value "Hole 14mm diameter")
      (footprint "Mounting Hole 14mm")
      (description "Hole for mounting")
      (libsource (lib "PilotMap_Main_Parts") (part "Mounting Hole 14mm"))
    )
    (comp (ref "MH19")
      (value "Hole 14mm diameter")
      (footprint "Mounting Hole 14mm")
      (description "Hole for mounting")
      (libsource (lib "PilotMap_Main_Parts") (part "Mounting Hole 14mm"))
    )
    (comp (ref "MH20")
      (value "Hole 14mm diameter")
      (footprint "Mounting Hole 14mm")
      (description "Hole for mounting")
      (libsource (lib "PilotMap_Main_Parts") (part "Mounting Hole 14mm"))
    )
    (comp (ref "MH21")
      (value "Hole 14mm diameter")
      (footprint "Mounting Hole 14mm")
      (description "Hole for mounting")
      (libsource (lib "PilotMap_Main_Parts") (part "Mounting Hole 14mm"))
    )
    (comp (ref "MH22")
      (value "Hole 12mm diameter")
      (footprint "Mounting Hole 12mm")
      (description "Hole for mounting")
      (libsource (lib "PilotMap_Main_Parts") (part "Mounting Hole 12mm"))
    )
    (comp (ref "MH23")
      (value "Hole 12mm diameter")
      (footprint "Mounting Hole 12mm")
      (description "Hole for mounting")
      (libsource (lib "PilotMap_Main_Parts") (part "Mounting Hole 12mm"))
    )
    (comp (ref "MH24")
      (value "Hole 12mm diameter")
      (footprint "Mounting Hole 12mm")
      (description "Hole for mounting")
      (libsource (lib "PilotMap_Main_Parts") (part "Mounting Hole 12mm"))
    )
    (comp (ref "MH25")
      (value "Hole 12mm diameter")
      (footprint "Mounting Hole 12mm")
      (description "Hole for mounting")
      (libsource (lib "PilotMap_Main_Parts") (part "Mounting Hole 12mm"))
    )
    (comp (ref "MH26")
      (value "Hole 12mm diameter")
      (footprint "Mounting Hole 12mm")
      (description "Hole for mounting")
      (libsource (lib "PilotMap_Main_Parts") (part "Mounting Hole 12mm"))
    )
    (comp (ref "MH27")
      (value "Hole 12mm diameter")
      (footprint "Mounting Hole 12mm")
      (description "Hole for mounting")
      (libsource (lib "PilotMap_Main_Parts") (part "Mounting Hole 12mm"))
    )
    (comp (ref "MH28")
      (value "Hole 14mm diameter")
      (footprint "Mounting Hole 14mm")
      (description "Hole for mounting")
      (libsource (lib "PilotMap_Main_Parts") (part "Mounting Hole 14mm"))
    )
    (comp (ref "Mounting Case 1")
      (value "Mounting Hole")
      (footprint "PCB-q0vxx67e01kaxtvhakkm-1")
      (description "Mounting Hole 3.5mm")
      (libsource (lib "PCB_Project") (part "CMP-q3gk3wg8yin1w7wp8pag-1"))
    )
    (comp (ref "Mounting Case 2")
      (value "Mounting Hole")
      (footprint "PCB-q0vxx67e01kaxtvhakkm-1")
      (description "Mounting Hole 3.5mm")
      (libsource (lib "PCB_Project") (part "CMP-q3gk3wg8yin1w7wp8pag-1"))
    )
    (comp (ref "Mounting Case 3")
      (value "Mounting Hole")
      (footprint "PCB-q0vxx67e01kaxtvhakkm-1")
      (description "Mounting Hole 3.5mm")
      (libsource (lib "PCB_Project") (part "CMP-q3gk3wg8yin1w7wp8pag-1"))
    )
    (comp (ref "Mounting Case 4")
      (value "Mounting Hole")
      (footprint "PCB-q0vxx67e01kaxtvhakkm-1")
      (description "Mounting Hole 3.5mm")
      (libsource (lib "PCB_Project") (part "CMP-q3gk3wg8yin1w7wp8pag-1"))
    )
    (comp (ref "Mounting Frame 1")
      (value "Mounting Hole")
      (footprint "PCB-q0vxx67e01kaxtvhakkm-1")
      (description "Mounting Hole 3.5mm")
      (libsource (lib "PCB_Project") (part "CMP-q3gk3wg8yin1w7wp8pag-1"))
    )
    (comp (ref "Mounting Frame 2")
      (value "Mounting Hole")
      (footprint "PCB-q0vxx67e01kaxtvhakkm-1")
      (description "Mounting Hole 3.5mm")
      (libsource (lib "PCB_Project") (part "CMP-q3gk3wg8yin1w7wp8pag-1"))
    )
    (comp (ref "Mounting Frame 3")
      (value "Mounting Hole")
      (footprint "PCB-q0vxx67e01kaxtvhakkm-1")
      (description "Mounting Hole 3.5mm")
      (libsource (lib "PCB_Project") (part "CMP-q3gk3wg8yin1w7wp8pag-1"))
    )
    (comp (ref "Mounting Frame 4")
      (value "Mounting Hole")
      (footprint "PCB-q0vxx67e01kaxtvhakkm-1")
      (description "Mounting Hole 3.5mm")
      (libsource (lib "PCB_Project") (part "CMP-q3gk3wg8yin1w7wp8pag-1"))
    )
    (comp (ref "Mounting Frame 5")
      (value "Mounting Hole")
      (footprint "PCB-q0vxx67e01kaxtvhakkm-1")
      (description "Mounting Hole 3.5mm")
      (libsource (lib "PCB_Project") (part "CMP-q3gk3wg8yin1w7wp8pag-1"))
    )
    (comp (ref "Mounting Frame 6")
      (value "Mounting Hole")
      (footprint "PCB-q0vxx67e01kaxtvhakkm-1")
      (description "Mounting Hole 3.5mm")
      (libsource (lib "PCB_Project") (part "CMP-q3gk3wg8yin1w7wp8pag-1"))
    )
    (comp (ref "Mounting Frame 7")
      (value "Mounting Hole")
      (footprint "PCB-q0vxx67e01kaxtvhakkm-1")
      (description "Mounting Hole 3.5mm")
      (libsource (lib "PCB_Project") (part "CMP-q3gk3wg8yin1w7wp8pag-1"))
    )
    (comp (ref "Mounting Frame 8")
      (value "Mounting Hole")
      (footprint "PCB-q0vxx67e01kaxtvhakkm-1")
      (description "Mounting Hole 3.5mm")
      (libsource (lib "PCB_Project") (part "CMP-q3gk3wg8yin1w7wp8pag-1"))
    )
    (comp (ref "Mounting Frame 9")
      (value "Mounting Hole")
      (footprint "PCB-q0vxx67e01kaxtvhakkm-1")
      (description "Mounting Hole 3.5mm")
      (libsource (lib "PCB_Project") (part "CMP-q3gk3wg8yin1w7wp8pag-1"))
    )
    (comp (ref "Mounting Frame 10")
      (value "Mounting Hole")
      (footprint "PCB-q0vxx67e01kaxtvhakkm-1")
      (description "Mounting Hole 3.5mm")
      (libsource (lib "PCB_Project") (part "CMP-q3gk3wg8yin1w7wp8pag-1"))
    )
    (comp (ref "Mounting Frame 11")
      (value "Mounting Hole")
      (footprint "PCB-q0vxx67e01kaxtvhakkm-1")
      (description "Mounting Hole 3.5mm")
      (libsource (lib "PCB_Project") (part "CMP-q3gk3wg8yin1w7wp8pag-1"))
    )
    (comp (ref "Mounting Frame 12")
      (value "Mounting Hole")
      (footprint "PCB-q0vxx67e01kaxtvhakkm-1")
      (description "Mounting Hole 3.5mm")
      (libsource (lib "PCB_Project") (part "CMP-q3gk3wg8yin1w7wp8pag-1"))
    )
    (comp (ref "Mount_foot1")
      (value "Mounting Hole")
      (footprint "PCB-q0vxx67e01kaxtvhakkm-1")
      (description "Mounting Hole 3.5mm")
      (libsource (lib "PCB_Project") (part "CMP-q3gk3wg8yin1w7wp8pag-1"))
    )
    (comp (ref "Mount_Foot2")
      (value "Mounting Hole")
      (footprint "PCB-q0vxx67e01kaxtvhakkm-1")
      (description "Mounting Hole 3.5mm")
      (libsource (lib "PCB_Project") (part "CMP-q3gk3wg8yin1w7wp8pag-1"))
    )
    (comp (ref "MVFR")
      (value "Worldsemi WS2812B-2020")
      (footprint "PCB-18681qzhn4j348g96a9l-1")
      (fields (field (name "MANUFACTURER PART NUMBER") "WS2812B-2020"))
      (libsource (lib "PCB_Project") (part "CMP-30b1feb25fa9ef76-6"))
    )
    (comp (ref "PABL")
      (value "Worldsemi WS2812B-2020")
      (footprint "PCB-18681qzhn4j348g96a9l-1")
      (fields (field (name "MANUFACTURER PART NUMBER") "WS2812B-2020"))
      (libsource (lib "PCB_Project") (part "CMP-30b1feb25fa9ef76-6"))
    )
    (comp (ref "PABR")
      (value "Worldsemi WS2812B-2020")
      (footprint "PCB-18681qzhn4j348g96a9l-1")
      (fields (field (name "MANUFACTURER PART NUMBER") "WS2812B-2020"))
      (libsource (lib "PCB_Project") (part "CMP-30b1feb25fa9ef76-6"))
    )
    (comp (ref "PABT")
      (value "Worldsemi WS2812B-2020")
      (footprint "PCB-18681qzhn4j348g96a9l-1")
      (fields (field (name "MANUFACTURER PART NUMBER") "WS2812B-2020"))
      (libsource (lib "PCB_Project") (part "CMP-30b1feb25fa9ef76-6"))
    )
    (comp (ref "PACM")
      (value "Worldsemi WS2812B-2020")
      (footprint "PCB-18681qzhn4j348g96a9l-1")
      (fields (field (name "MANUFACTURER PART NUMBER") "WS2812B-2020"))
      (libsource (lib "PCB_Project") (part "CMP-30b1feb25fa9ef76-6"))
    )
    (comp (ref "PACX")
      (value "Worldsemi WS2812B-2020")
      (footprint "PCB-18681qzhn4j348g96a9l-1")
      (fields (field (name "MANUFACTURER PART NUMBER") "WS2812B-2020"))
      (libsource (lib "PCB_Project") (part "CMP-30b1feb25fa9ef76-6"))
    )
    (comp (ref "PACZ")
      (value "Worldsemi WS2812B-2020")
      (footprint "PCB-18681qzhn4j348g96a9l-1")
      (fields (field (name "MANUFACTURER PART NUMBER") "WS2812B-2020"))
      (libsource (lib "PCB_Project") (part "CMP-30b1feb25fa9ef76-6"))
    )
    (comp (ref "PADE")
      (value "Worldsemi WS2812B-2020")
      (footprint "PCB-18681qzhn4j348g96a9l-1")
      (fields (field (name "MANUFACTURER PART NUMBER") "WS2812B-2020"))
      (libsource (lib "PCB_Project") (part "CMP-30b1feb25fa9ef76-6"))
    )
    (comp (ref "PADG")
      (value "Worldsemi WS2812B-2020")
      (footprint "PCB-18681qzhn4j348g96a9l-1")
      (fields (field (name "MANUFACTURER PART NUMBER") "WS2812B-2020"))
      (libsource (lib "PCB_Project") (part "CMP-30b1feb25fa9ef76-6"))
    )
    (comp (ref "PADM")
      (value "Worldsemi WS2812B-2020")
      (footprint "PCB-18681qzhn4j348g96a9l-1")
      (fields (field (name "MANUFACTURER PART NUMBER") "WS2812B-2020"))
      (libsource (lib "PCB_Project") (part "CMP-30b1feb25fa9ef76-6"))
    )
    (comp (ref "PAFA")
      (value "Worldsemi WS2812B-2020")
      (footprint "PCB-18681qzhn4j348g96a9l-1")
      (fields (field (name "MANUFACTURER PART NUMBER") "WS2812B-2020"))
      (libsource (lib "PCB_Project") (part "CMP-30b1feb25fa9ef76-6"))
    )
    (comp (ref "PAFB")
      (value "Worldsemi WS2812B-2020")
      (footprint "PCB-18681qzhn4j348g96a9l-1")
      (fields (field (name "MANUFACTURER PART NUMBER") "WS2812B-2020"))
      (libsource (lib "PCB_Project") (part "CMP-30b1feb25fa9ef76-6"))
    )
    (comp (ref "PAFM")
      (value "Worldsemi WS2812B-2020")
      (footprint "PCB-18681qzhn4j348g96a9l-1")
      (fields (field (name "MANUFACTURER PART NUMBER") "WS2812B-2020"))
      (libsource (lib "PCB_Project") (part "CMP-30b1feb25fa9ef76-6"))
    )
    (comp (ref "PAFS")
      (value "Worldsemi WS2812B-2020")
      (footprint "PCB-18681qzhn4j348g96a9l-1")
      (fields (field (name "MANUFACTURER PART NUMBER") "WS2812B-2020"))
      (libsource (lib "PCB_Project") (part "CMP-30b1feb25fa9ef76-6"))
    )
    (comp (ref "PAGA")
      (value "Worldsemi WS2812B-2020")
      (footprint "PCB-18681qzhn4j348g96a9l-1")
      (fields (field (name "MANUFACTURER PART NUMBER") "WS2812B-2020"))
      (libsource (lib "PCB_Project") (part "CMP-30b1feb25fa9ef76-6"))
    )
    (comp (ref "PAGB")
      (value "Worldsemi WS2812B-2020")
      (footprint "PCB-18681qzhn4j348g96a9l-1")
      (fields (field (name "MANUFACTURER PART NUMBER") "WS2812B-2020"))
      (libsource (lib "PCB_Project") (part "CMP-30b1feb25fa9ef76-6"))
    )
    (comp (ref "PAGH")
      (value "Worldsemi WS2812B-2020")
      (footprint "PCB-18681qzhn4j348g96a9l-1")
      (fields (field (name "MANUFACTURER PART NUMBER") "WS2812B-2020"))
      (libsource (lib "PCB_Project") (part "CMP-30b1feb25fa9ef76-6"))
    )
    (comp (ref "PAGL")
      (value "Worldsemi WS2812B-2020")
      (footprint "PCB-18681qzhn4j348g96a9l-1")
      (fields (field (name "MANUFACTURER PART NUMBER") "WS2812B-2020"))
      (libsource (lib "PCB_Project") (part "CMP-30b1feb25fa9ef76-6"))
    )
    (comp (ref "PAHC")
      (value "Worldsemi WS2812B-2020")
      (footprint "PCB-18681qzhn4j348g96a9l-1")
      (fields (field (name "MANUFACTURER PART NUMBER") "WS2812B-2020"))
      (libsource (lib "PCB_Project") (part "CMP-30b1feb25fa9ef76-6"))
    )
    (comp (ref "PAHL")
      (value "Worldsemi WS2812B-2020")
      (footprint "PCB-18681qzhn4j348g96a9l-1")
      (fields (field (name "MANUFACTURER PART NUMBER") "WS2812B-2020"))
      (libsource (lib "PCB_Project") (part "CMP-30b1feb25fa9ef76-6"))
    )
    (comp (ref "PAHX")
      (value "Worldsemi WS2812B-2020")
      (footprint "PCB-18681qzhn4j348g96a9l-1")
      (fields (field (name "MANUFACTURER PART NUMBER") "WS2812B-2020"))
      (libsource (lib "PCB_Project") (part "CMP-30b1feb25fa9ef76-6"))
    )
    (comp (ref "PAIK")
      (value "Worldsemi WS2812B-2020")
      (footprint "PCB-18681qzhn4j348g96a9l-1")
      (fields (field (name "MANUFACTURER PART NUMBER") "WS2812B-2020"))
      (libsource (lib "PCB_Project") (part "CMP-30b1feb25fa9ef76-6"))
    )
    (comp (ref "PAIM")
      (value "Worldsemi WS2812B-2020")
      (footprint "PCB-18681qzhn4j348g96a9l-1")
      (fields (field (name "MANUFACTURER PART NUMBER") "WS2812B-2020"))
      (libsource (lib "PCB_Project") (part "CMP-30b1feb25fa9ef76-6"))
    )
    (comp (ref "PAIN")
      (value "Worldsemi WS2812B-2020")
      (footprint "PCB-18681qzhn4j348g96a9l-1")
      (fields (field (name "MANUFACTURER PART NUMBER") "WS2812B-2020"))
      (libsource (lib "PCB_Project") (part "CMP-30b1feb25fa9ef76-6"))
    )
    (comp (ref "PAIW")
      (value "Worldsemi WS2812B-2020")
      (footprint "PCB-18681qzhn4j348g96a9l-1")
      (fields (field (name "MANUFACTURER PART NUMBER") "WS2812B-2020"))
      (libsource (lib "PCB_Project") (part "CMP-30b1feb25fa9ef76-6"))
    )
    (comp (ref "PAKK")
      (value "Worldsemi WS2812B-2020")
      (footprint "PCB-18681qzhn4j348g96a9l-1")
      (fields (field (name "MANUFACTURER PART NUMBER") "WS2812B-2020"))
      (libsource (lib "PCB_Project") (part "CMP-30b1feb25fa9ef76-6"))
    )
    (comp (ref "PAKP")
      (value "Worldsemi WS2812B-2020")
      (footprint "PCB-18681qzhn4j348g96a9l-1")
      (fields (field (name "MANUFACTURER PART NUMBER") "WS2812B-2020"))
      (libsource (lib "PCB_Project") (part "CMP-30b1feb25fa9ef76-6"))
    )
    (comp (ref "PAKU")
      (value "Worldsemi WS2812B-2020")
      (footprint "PCB-18681qzhn4j348g96a9l-1")
      (fields (field (name "MANUFACTURER PART NUMBER") "WS2812B-2020"))
      (libsource (lib "PCB_Project") (part "CMP-30b1feb25fa9ef76-6"))
    )
    (comp (ref "PAKV")
      (value "Worldsemi WS2812B-2020")
      (footprint "PCB-18681qzhn4j348g96a9l-1")
      (fields (field (name "MANUFACTURER PART NUMBER") "WS2812B-2020"))
      (libsource (lib "PCB_Project") (part "CMP-30b1feb25fa9ef76-6"))
    )
    (comp (ref "PALP")
      (value "Worldsemi WS2812B-2020")
      (footprint "PCB-18681qzhn4j348g96a9l-1")
      (fields (field (name "MANUFACTURER PART NUMBER") "WS2812B-2020"))
      (libsource (lib "PCB_Project") (part "CMP-30b1feb25fa9ef76-6"))
    )
    (comp (ref "PALU")
      (value "Worldsemi WS2812B-2020")
      (footprint "PCB-18681qzhn4j348g96a9l-1")
      (fields (field (name "MANUFACTURER PART NUMBER") "WS2812B-2020"))
      (libsource (lib "PCB_Project") (part "CMP-30b1feb25fa9ef76-6"))
    )
    (comp (ref "PAMC")
      (value "Worldsemi WS2812B-2020")
      (footprint "PCB-18681qzhn4j348g96a9l-1")
      (fields (field (name "MANUFACTURER PART NUMBER") "WS2812B-2020"))
      (libsource (lib "PCB_Project") (part "CMP-30b1feb25fa9ef76-6"))
    )
    (comp (ref "PAMH")
      (value "Worldsemi WS2812B-2020")
      (footprint "PCB-18681qzhn4j348g96a9l-1")
      (fields (field (name "MANUFACTURER PART NUMBER") "WS2812B-2020"))
      (libsource (lib "PCB_Project") (part "CMP-30b1feb25fa9ef76-6"))
    )
    (comp (ref "PAMK")
      (value "Worldsemi WS2812B-2020")
      (footprint "PCB-18681qzhn4j348g96a9l-1")
      (fields (field (name "MANUFACTURER PART NUMBER") "WS2812B-2020"))
      (libsource (lib "PCB_Project") (part "CMP-30b1feb25fa9ef76-6"))
    )
    (comp (ref "PAMO")
      (value "Worldsemi WS2812B-2020")
      (footprint "PCB-18681qzhn4j348g96a9l-1")
      (fields (field (name "MANUFACTURER PART NUMBER") "WS2812B-2020"))
      (libsource (lib "PCB_Project") (part "CMP-30b1feb25fa9ef76-6"))
    )
    (comp (ref "PANN")
      (value "Worldsemi WS2812B-2020")
      (footprint "PCB-18681qzhn4j348g96a9l-1")
      (fields (field (name "MANUFACTURER PART NUMBER") "WS2812B-2020"))
      (libsource (lib "PCB_Project") (part "CMP-30b1feb25fa9ef76-6"))
    )
    (comp (ref "PANU")
      (value "Worldsemi WS2812B-2020")
      (footprint "PCB-18681qzhn4j348g96a9l-1")
      (fields (field (name "MANUFACTURER PART NUMBER") "WS2812B-2020"))
      (libsource (lib "PCB_Project") (part "CMP-30b1feb25fa9ef76-6"))
    )
    (comp (ref "PANV")
      (value "Worldsemi WS2812B-2020")
      (footprint "PCB-18681qzhn4j348g96a9l-1")
      (fields (field (name "MANUFACTURER PART NUMBER") "WS2812B-2020"))
      (libsource (lib "PCB_Project") (part "CMP-30b1feb25fa9ef76-6"))
    )
    (comp (ref "PAOM")
      (value "Worldsemi WS2812B-2020")
      (footprint "PCB-18681qzhn4j348g96a9l-1")
      (fields (field (name "MANUFACTURER PART NUMBER") "WS2812B-2020"))
      (libsource (lib "PCB_Project") (part "CMP-30b1feb25fa9ef76-6"))
    )
    (comp (ref "PAOT")
      (value "Worldsemi WS2812B-2020")
      (footprint "PCB-18681qzhn4j348g96a9l-1")
      (fields (field (name "MANUFACTURER PART NUMBER") "WS2812B-2020"))
      (libsource (lib "PCB_Project") (part "CMP-30b1feb25fa9ef76-6"))
    )
    (comp (ref "PAPO")
      (value "Worldsemi WS2812B-2020")
      (footprint "PCB-18681qzhn4j348g96a9l-1")
      (fields (field (name "MANUFACTURER PART NUMBER") "WS2812B-2020"))
      (libsource (lib "PCB_Project") (part "CMP-30b1feb25fa9ef76-6"))
    )
    (comp (ref "PAPR")
      (value "Worldsemi WS2812B-2020")
      (footprint "PCB-18681qzhn4j348g96a9l-1")
      (fields (field (name "MANUFACTURER PART NUMBER") "WS2812B-2020"))
      (libsource (lib "PCB_Project") (part "CMP-30b1feb25fa9ef76-6"))
    )
    (comp (ref "PAQT")
      (value "Worldsemi WS2812B-2020")
      (footprint "PCB-18681qzhn4j348g96a9l-1")
      (fields (field (name "MANUFACTURER PART NUMBER") "WS2812B-2020"))
      (libsource (lib "PCB_Project") (part "CMP-30b1feb25fa9ef76-6"))
    )
    (comp (ref "PARS")
      (value "Worldsemi WS2812B-2020")
      (footprint "PCB-18681qzhn4j348g96a9l-1")
      (fields (field (name "MANUFACTURER PART NUMBER") "WS2812B-2020"))
      (libsource (lib "PCB_Project") (part "CMP-30b1feb25fa9ef76-6"))
    )
    (comp (ref "PARY")
      (value "Worldsemi WS2812B-2020")
      (footprint "PCB-18681qzhn4j348g96a9l-1")
      (fields (field (name "MANUFACTURER PART NUMBER") "WS2812B-2020"))
      (libsource (lib "PCB_Project") (part "CMP-30b1feb25fa9ef76-6"))
    )
    (comp (ref "PASH")
      (value "Worldsemi WS2812B-2020")
      (footprint "PCB-18681qzhn4j348g96a9l-1")
      (fields (field (name "MANUFACTURER PART NUMBER") "WS2812B-2020"))
      (libsource (lib "PCB_Project") (part "CMP-30b1feb25fa9ef76-6"))
    )
    (comp (ref "PASK")
      (value "Worldsemi WS2812B-2020")
      (footprint "PCB-18681qzhn4j348g96a9l-1")
      (fields (field (name "MANUFACTURER PART NUMBER") "WS2812B-2020"))
      (libsource (lib "PCB_Project") (part "CMP-30b1feb25fa9ef76-6"))
    )
    (comp (ref "PASM")
      (value "Worldsemi WS2812B-2020")
      (footprint "PCB-18681qzhn4j348g96a9l-1")
      (fields (field (name "MANUFACTURER PART NUMBER") "WS2812B-2020"))
      (libsource (lib "PCB_Project") (part "CMP-30b1feb25fa9ef76-6"))
    )
    (comp (ref "PATA")
      (value "Worldsemi WS2812B-2020")
      (footprint "PCB-18681qzhn4j348g96a9l-1")
      (fields (field (name "MANUFACTURER PART NUMBER") "WS2812B-2020"))
      (libsource (lib "PCB_Project") (part "CMP-30b1feb25fa9ef76-6"))
    )
    (comp (ref "PATC")
      (value "Worldsemi WS2812B-2020")
      (footprint "PCB-18681qzhn4j348g96a9l-1")
      (fields (field (name "MANUFACTURER PART NUMBER") "WS2812B-2020"))
      (libsource (lib "PCB_Project") (part "CMP-30b1feb25fa9ef76-6"))
    )
    (comp (ref "PATE")
      (value "Worldsemi WS2812B-2020")
      (footprint "PCB-18681qzhn4j348g96a9l-1")
      (fields (field (name "MANUFACTURER PART NUMBER") "WS2812B-2020"))
      (libsource (lib "PCB_Project") (part "CMP-30b1feb25fa9ef76-6"))
    )
    (comp (ref "PATL")
      (value "Worldsemi WS2812B-2020")
      (footprint "PCB-18681qzhn4j348g96a9l-1")
      (fields (field (name "MANUFACTURER PART NUMBER") "WS2812B-2020"))
      (libsource (lib "PCB_Project") (part "CMP-30b1feb25fa9ef76-6"))
    )
    (comp (ref "PATQ")
      (value "Worldsemi WS2812B-2020")
      (footprint "PCB-18681qzhn4j348g96a9l-1")
      (fields (field (name "MANUFACTURER PART NUMBER") "WS2812B-2020"))
      (libsource (lib "PCB_Project") (part "CMP-30b1feb25fa9ef76-6"))
    )
    (comp (ref "PAUN")
      (value "Worldsemi WS2812B-2020")
      (footprint "PCB-18681qzhn4j348g96a9l-1")
      (fields (field (name "MANUFACTURER PART NUMBER") "WS2812B-2020"))
      (libsource (lib "PCB_Project") (part "CMP-30b1feb25fa9ef76-6"))
    )
    (comp (ref "PAVA")
      (value "Worldsemi WS2812B-2020")
      (footprint "PCB-18681qzhn4j348g96a9l-1")
      (fields (field (name "MANUFACTURER PART NUMBER") "WS2812B-2020"))
      (libsource (lib "PCB_Project") (part "CMP-30b1feb25fa9ef76-6"))
    )
    (comp (ref "PAVL")
      (value "Worldsemi WS2812B-2020")
      (footprint "PCB-18681qzhn4j348g96a9l-1")
      (fields (field (name "MANUFACTURER PART NUMBER") "WS2812B-2020"))
      (libsource (lib "PCB_Project") (part "CMP-30b1feb25fa9ef76-6"))
    )
    (comp (ref "PAWM")
      (value "Worldsemi WS2812B-2020")
      (footprint "PCB-18681qzhn4j348g96a9l-1")
      (fields (field (name "MANUFACTURER PART NUMBER") "WS2812B-2020"))
      (libsource (lib "PCB_Project") (part "CMP-30b1feb25fa9ef76-6"))
    )
    (comp (ref "PAWN")
      (value "Worldsemi WS2812B-2020")
      (footprint "PCB-18681qzhn4j348g96a9l-1")
      (fields (field (name "MANUFACTURER PART NUMBER") "WS2812B-2020"))
      (libsource (lib "PCB_Project") (part "CMP-30b1feb25fa9ef76-6"))
    )
    (comp (ref "PFEL")
      (value "Worldsemi WS2812B-2020")
      (footprint "PCB-18681qzhn4j348g96a9l-1")
      (fields (field (name "MANUFACTURER PART NUMBER") "WS2812B-2020"))
      (libsource (lib "PCB_Project") (part "CMP-30b1feb25fa9ef76-6"))
    )
    (comp (ref "PFKT")
      (value "Worldsemi WS2812B-2020")
      (footprint "PCB-18681qzhn4j348g96a9l-1")
      (fields (field (name "MANUFACTURER PART NUMBER") "WS2812B-2020"))
      (libsource (lib "PCB_Project") (part "CMP-30b1feb25fa9ef76-6"))
    )
    (comp (ref "PFSH")
      (value "Worldsemi WS2812B-2020")
      (footprint "PCB-18681qzhn4j348g96a9l-1")
      (fields (field (name "MANUFACTURER PART NUMBER") "WS2812B-2020"))
      (libsource (lib "PCB_Project") (part "CMP-30b1feb25fa9ef76-6"))
    )
    (comp (ref "Power / LED in1")
      (value "TE Connectivity 282836-3")
      (footprint "282836-3")
      (description "Conn; Term Blk; Wire Receptacle; 3; 5 mm; 30-16 AWG; Green; 13.5 A; 300 V")
      (fields (field (name "MANUFACTURER PART NUMBER") "282836-3"))
      (libsource (lib "") (part "CMP-d7c21c93a45c0805-15_1"))
    )
    (comp (ref "Power / LED out1")
      (value "TE Connectivity 282836-3")
      (footprint "282836-3")
      (description "Conn; Term Blk; Wire Receptacle; 3; 5 mm; 30-16 AWG; Green; 13.5 A; 300 V")
      (fields (field (name "MANUFACTURER PART NUMBER") "282836-3"))
      (libsource (lib "PCB_Project") (part "CMP-d7c21c93a45c0805-15"))
    )
    (comp (ref "Power Conn1")
      (value "CMP-330397-12")
      (footprint "PCB-h5dulpljww4oyv25n50t-1")
      (description "CUI PJ-037A")
      (libsource (lib "PCB_Project") (part "CMP-330397-12"))
    )
    (comp (ref "PPIZ")
      (value "Worldsemi WS2812B-2020")
      (footprint "PCB-18681qzhn4j348g96a9l-1")
      (fields (field (name "MANUFACTURER PART NUMBER") "WS2812B-2020"))
      (libsource (lib "PCB_Project") (part "CMP-30b1feb25fa9ef76-6"))
    )
    (comp (ref "R1")
      (value "5.1k 0603")
      (footprint "CAPC1608X90X35NL15T15")
      (description "Res Thick Film 0603 5.1K Ohm 1% 1/10W ±100ppm/°C Molded SMD SMD Punched Carrier T/R")
      (fields (field (name "MANUFACTURER PART NUMBER") "ERJ-3EKF5101V"))
      (libsource (lib "PCB_Project") (part "CMP-3656428-4"))
    )
    (comp (ref "R2")
      (value "5.1k 0603")
      (footprint "CAPC1608X90X35NL15T15")
      (description "Res Thick Film 0603 5.1K Ohm 1% 1/10W ±100ppm/°C Molded SMD SMD Punched Carrier T/R")
      (fields (field (name "MANUFACTURER PART NUMBER") "ERJ-3EKF5101V"))
      (libsource (lib "PCB_Project") (part "CMP-3656428-4"))
    )
    (comp (ref "Side1")
      (value "Mounting Hole")
      (footprint "PCB-q0vxx67e01kaxtvhakkm-1")
      (description "Mounting Hole 3.5mm")
      (libsource (lib "PCB_Project") (part "CMP-q3gk3wg8yin1w7wp8pag-1"))
    )
    (comp (ref "Side2")
      (value "Mounting Hole")
      (footprint "PCB-q0vxx67e01kaxtvhakkm-1")
      (description "Mounting Hole 3.5mm")
      (libsource (lib "PCB_Project") (part "CMP-q3gk3wg8yin1w7wp8pag-1"))
    )
    (comp (ref "Side3")
      (value "Mounting Hole")
      (footprint "PCB-q0vxx67e01kaxtvhakkm-1")
      (description "Mounting Hole 3.5mm")
      (libsource (lib "PCB_Project") (part "CMP-q3gk3wg8yin1w7wp8pag-1"))
    )
    (comp (ref "Side4")
      (value "Mounting Hole")
      (footprint "PCB-q0vxx67e01kaxtvhakkm-1")
      (description "Mounting Hole 3.5mm")
      (libsource (lib "PCB_Project") (part "CMP-q3gk3wg8yin1w7wp8pag-1"))
    )
    (comp (ref "Side5")
      (value "Mounting Hole")
      (footprint "PCB-q0vxx67e01kaxtvhakkm-1")
      (description "Mounting Hole 3.5mm")
      (libsource (lib "PCB_Project") (part "CMP-q3gk3wg8yin1w7wp8pag-1"))
    )
    (comp (ref "Side6")
      (value "Mounting Hole")
      (footprint "PCB-q0vxx67e01kaxtvhakkm-1")
      (description "Mounting Hole 3.5mm")
      (libsource (lib "PCB_Project") (part "CMP-q3gk3wg8yin1w7wp8pag-1"))
    )
    (comp (ref "Side7")
      (value "Mounting Hole")
      (footprint "PCB-q0vxx67e01kaxtvhakkm-1")
      (description "Mounting Hole 3.5mm")
      (libsource (lib "PCB_Project") (part "CMP-q3gk3wg8yin1w7wp8pag-1"))
    )
    (comp (ref "Side8")
      (value "Mounting Hole")
      (footprint "PCB-q0vxx67e01kaxtvhakkm-1")
      (description "Mounting Hole 3.5mm")
      (libsource (lib "PCB_Project") (part "CMP-q3gk3wg8yin1w7wp8pag-1"))
    )
    (comp (ref "U1")
      (value "TI (Texas Instruments) SN74AHCT125PWR")
      (footprint "PCB-19361381-1")
      (description "IC BUS BUFFER TRI-ST QD 14TSSOP")
      (fields (field (name "MANUFACTURER PART NUMBER") "SN74AHCT125PWR"))
      (libsource (lib "PCB_Project") (part "CMP-13613041-2"))
    )
    (comp (ref "U2")
      (value "Texas Instruments SN74AHCT125DR")
      (footprint "PCB-4n9l8bvb0hxmq9svv09s-1")
      (description "Buffer/Line Driver 4-CH Non-Inverting 3-ST CMOS 14-Pin SOIC T/R")
      (fields (field (name "MANUFACTURER PART NUMBER") "SN74AHCT125DR"))
      (libsource (lib "PCB_Project") (part "CMP-35ebfce60942ea2c-2"))
    )
    (comp (ref "USB-C1")
      (value "Hooya USB-310M-B-SU")
      (footprint "Hooya USB-310M-B-SU-Footprint-1")
      (description "3A 1 Surface Mount 16 Female Type-C SMD USB Connector ROHS")
      (fields (field (name "MANUFACTURER PART NUMBER") "USB-310M-B-SU"))
      (libsource (lib "PCB_Project") (part "CMP-967358be92de49b4-1"))
    )
    (comp (ref "VFR")
      (value "Worldsemi WS2812B-2020")
      (footprint "PCB-18681qzhn4j348g96a9l-1")
      (fields (field (name "MANUFACTURER PART NUMBER") "WS2812B-2020"))
      (libsource (lib "PCB_Project") (part "CMP-30b1feb25fa9ef76-6"))
    )
  )
  (nets
    (net (code "1") (name "/1A") (class "Default")
      (node (ref "CPU Con1") (pin "11") (pinfunction "11_11") (pintype "passive"))
      (node (ref "CPU-Con1") (pin "6") (pinfunction "6_6") (pintype "passive"))
      (node (ref "Connector In1") (pin "3") (pinfunction "3_3") (pintype "passive"))
      (node (ref "Connector In1") (pin "8") (pinfunction "8_8") (pintype "passive"))
      (node (ref "Power / LED in1") (pin "2") (pinfunction "2_2") (pintype "passive"))
      (node (ref "U1") (pin "2") (pinfunction "1A_2") (pintype "passive"))
      (node (ref "U2") (pin "2") (pinfunction "1A_2") (pintype "passive"))
    )
    (net (code "2") (name "/GND") (class "Default")
      (node (ref "C1") (pin "2") (pinfunction "2_2") (pintype "passive"))
      (node (ref "C10") (pin "2") (pinfunction "2_2") (pintype "passive"))
      (node (ref "C11") (pin "2") (pinfunction "2_2") (pintype "passive"))
      (node (ref "C12") (pin "2") (pinfunction "2_2") (pintype "passive"))
      (node (ref "C13") (pin "2") (pinfunction "2_2") (pintype "passive"))
      (node (ref "C14") (pin "2") (pinfunction "2_2") (pintype "passive"))
      (node (ref "C15") (pin "2") (pinfunction "2_2") (pintype "passive"))
      (node (ref "C16") (pin "2") (pinfunction "2_2") (pintype "passive"))
      (node (ref "C17") (pin "2") (pinfunction "2_2") (pintype "passive"))
      (node (ref "C18") (pin "2") (pinfunction "2_2") (pintype "passive"))
      (node (ref "C19") (pin "2") (pinfunction "2_2") (pintype "passive"))
      (node (ref "C2") (pin "2") (pinfunction "2_2") (pintype "passive"))
      (node (ref "C20") (pin "2") (pinfunction "2_2") (pintype "passive"))
      (node (ref "C21") (pin "2") (pinfunction "2_2") (pintype "passive"))
      (node (ref "C22") (pin "2") (pinfunction "2_2") (pintype "passive"))
      (node (ref "C23") (pin "2") (pinfunction "2_2") (pintype "passive"))
      (node (ref "C24") (pin "2") (pinfunction "2_2") (pintype "passive"))
      (node (ref "C25") (pin "2") (pinfunction "2_2") (pintype "passive"))
      (node (ref "C26") (pin "2") (pinfunction "2_2") (pintype "passive"))
      (node (ref "C27") (pin "2") (pinfunction "2_2") (pintype "passive"))
      (node (ref "C28") (pin "2") (pinfunction "2_2") (pintype "passive"))
      (node (ref "C29") (pin "2") (pinfunction "2_2") (pintype "passive"))
      (node (ref "C3") (pin "2") (pinfunction "2_2") (pintype "passive"))
      (node (ref "C30") (pin "2") (pinfunction "2_2") (pintype "passive"))
      (node (ref "C31") (pin "2") (pinfunction "2_2") (pintype "passive"))
      (node (ref "C32") (pin "2") (pinfunction "2_2") (pintype "passive"))
      (node (ref "C33") (pin "2") (pinfunction "2_2") (pintype "passive"))
      (node (ref "C34") (pin "2") (pinfunction "2_2") (pintype "passive"))
      (node (ref "C35") (pin "2") (pinfunction "2_2") (pintype "passive"))
      (node (ref "C36") (pin "2") (pinfunction "2_2") (pintype "passive"))
      (node (ref "C37") (pin "2") (pinfunction "2_2") (pintype "passive"))
      (node (ref "C38") (pin "2") (pinfunction "2_2") (pintype "passive"))
      (node (ref "C39") (pin "2") (pinfunction "2_2") (pintype "passive"))
      (node (ref "C4") (pin "2") (pinfunction "2_2") (pintype "passive"))
      (node (ref "C40") (pin "2") (pinfunction "2_2") (pintype "passive"))
      (node (ref "C41") (pin "2") (pinfunction "2_2") (pintype "passive"))
      (node (ref "C42") (pin "2") (pinfunction "2_2") (pintype "passive"))
      (node (ref "C43") (pin "2") (pinfunction "2_2") (pintype "passive"))
      (node (ref "C44") (pin "2") (pinfunction "2_2") (pintype "passive"))
      (node (ref "C45") (pin "2") (pinfunction "2_2") (pintype "passive"))
      (node (ref "C46") (pin "2") (pinfunction "2_2") (pintype "passive"))
      (node (ref "C47") (pin "2") (pinfunction "2_2") (pintype "passive"))
      (node (ref "C48") (pin "2") (pinfunction "2_2") (pintype "passive"))
      (node (ref "C49") (pin "2") (pinfunction "2_2") (pintype "passive"))
      (node (ref "C5") (pin "2") (pinfunction "2_2") (pintype "passive"))
      (node (ref "C50") (pin "2") (pinfunction "2_2") (pintype "passive"))
      (node (ref "C51") (pin "2") (pinfunction "2_2") (pintype "passive"))
      (node (ref "C52") (pin "2") (pinfunction "2_2") (pintype "passive"))
      (node (ref "C53") (pin "2") (pinfunction "2_2") (pintype "passive"))
      (node (ref "C54") (pin "2") (pinfunction "2_2") (pintype "passive"))
      (node (ref "C55") (pin "2") (pinfunction "2_2") (pintype "passive"))
      (node (ref "C56") (pin "2") (pinfunction "2_2") (pintype "passive"))
      (node (ref "C57") (pin "2") (pinfunction "2_2") (pintype "passive"))
      (node (ref "C58") (pin "2") (pinfunction "2_2") (pintype "passive"))
      (node (ref "C59") (pin "2") (pinfunction "2_2") (pintype "passive"))
      (node (ref "C6") (pin "2") (pinfunction "2_2") (pintype "passive"))
      (node (ref "C60") (pin "2") (pinfunction "2_2") (pintype "passive"))
      (node (ref "C61") (pin "2") (pinfunction "2_2") (pintype "passive"))
      (node (ref "C62") (pin "2") (pinfunction "2_2") (pintype "passive"))
      (node (ref "C63") (pin "2") (pinfunction "2_2") (pintype "passive"))
      (node (ref "C64") (pin "2") (pinfunction "2_2") (pintype "passive"))
      (node (ref "C65") (pin "2") (pinfunction "2_2") (pintype "passive"))
      (node (ref "C66") (pin "2") (pinfunction "2_2") (pintype "passive"))
      (node (ref "C67") (pin "2") (pinfunction "2_2") (pintype "passive"))
      (node (ref "C68") (pin "2") (pinfunction "2_2") (pintype "passive"))
      (node (ref "C69") (pin "2") (pinfunction "2_2") (pintype "passive"))
      (node (ref "C7") (pin "2") (pinfunction "2_2") (pintype "passive"))
      (node (ref "C8") (pin "2") (pinfunction "2_2") (pintype "passive"))
      (node (ref "C9") (pin "2") (pinfunction "2_2") (pintype "passive"))
      (node (ref "CPU Con1") (pin "10") (pinfunction "10_10") (pintype "passive"))
      (node (ref "CPU Con1") (pin "13") (pinfunction "13_13") (pintype "passive"))
      (node (ref "CPU Con1") (pin "19") (pinfunction "19_19") (pintype "passive"))
      (node (ref "CPU Con1") (pin "26") (pinfunction "26_26") (pintype "passive"))
      (node (ref "CPU Con1") (pin "29") (pinfunction "29_29") (pintype "passive"))
      (node (ref "CPU Con1") (pin "33") (pinfunction "33_33") (pintype "passive"))
      (node (ref "CPU Con1") (pin "40") (pinfunction "40_40") (pintype "passive"))
      (node (ref "CPU Con1") (pin "5") (pinfunction "5_5") (pintype "passive"))
      (node (ref "CPU-Con1") (pin "10") (pinfunction "10_10") (pintype "passive"))
      (node (ref "CPU-Con1") (pin "15") (pinfunction "15_15") (pintype "passive"))
      (node (ref "CPU-Con1") (pin "17") (pinfunction "17_17") (pintype "passive"))
      (node (ref "CPU-Con1") (pin "25") (pinfunction "25_25") (pintype "passive"))
      (node (ref "CPU-Con1") (pin "3") (pinfunction "3_3") (pintype "passive"))
      (node (ref "CPU-Con1") (pin "33") (pinfunction "33_33") (pintype "passive"))
      (node (ref "CPU-Con1") (pin "40") (pinfunction "40_40") (pintype "passive"))
      (node (ref "CPU-Con1") (pin "7") (pinfunction "7_7") (pintype "passive"))
      (node (ref "Connector In1") (pin "1") (pinfunction "1_1") (pintype "passive"))
      (node (ref "Connector In1") (pin "2") (pinfunction "2_2") (pintype "passive"))
      (node (ref "Connector In1") (pin "6") (pinfunction "6_6") (pintype "passive"))
      (node (ref "Connector In1") (pin "7") (pinfunction "7_7") (pintype "passive"))
      (node (ref "Connector Out1") (pin "1") (pinfunction "1_1") (pintype "passive"))
      (node (ref "Connector Out1") (pin "2") (pinfunction "2_2") (pintype "passive"))
      (node (ref "Connector Out1") (pin "6") (pinfunction "6_6") (pintype "passive"))
      (node (ref "Connector Out1") (pin "7") (pinfunction "7_7") (pintype "passive"))
      (node (ref "IFR") (pin "2") (pinfunction "GND_2") (pintype "passive"))
      (node (ref "INVALID") (pin "2") (pinfunction "GND_2") (pintype "passive"))
      (node (ref "LIFR") (pin "2") (pinfunction "GND_2") (pintype "passive"))
      (node (ref "MVFR") (pin "2") (pinfunction "GND_2") (pintype "passive"))
      (node (ref "PABL") (pin "2") (pinfunction "GND_2") (pintype "passive"))
      (node (ref "PABR") (pin "2") (pinfunction "GND_2") (pintype "passive"))
      (node (ref "PABT") (pin "2") (pinfunction "GND_2") (pintype "passive"))
      (node (ref "PACM") (pin "2") (pinfunction "GND_2") (pintype "passive"))
      (node (ref "PACX") (pin "2") (pinfunction "GND_2") (pintype "passive"))
      (node (ref "PACZ") (pin "2") (pinfunction "GND_2") (pintype "passive"))
      (node (ref "PADE") (pin "2") (pinfunction "GND_2") (pintype "passive"))
      (node (ref "PADG") (pin "2") (pinfunction "GND_2") (pintype "passive"))
      (node (ref "PADM") (pin "2") (pinfunction "GND_2") (pintype "passive"))
      (node (ref "PAFA") (pin "2") (pinfunction "GND_2") (pintype "passive"))
      (node (ref "PAFB") (pin "2") (pinfunction "GND_2") (pintype "passive"))
      (node (ref "PAFM") (pin "2") (pinfunction "GND_2") (pintype "passive"))
      (node (ref "PAFS") (pin "2") (pinfunction "GND_2") (pintype "passive"))
      (node (ref "PAGA") (pin "2") (pinfunction "GND_2") (pintype "passive"))
      (node (ref "PAGB") (pin "2") (pinfunction "GND_2") (pintype "passive"))
      (node (ref "PAGH") (pin "2") (pinfunction "GND_2") (pintype "passive"))
      (node (ref "PAGL") (pin "2") (pinfunction "GND_2") (pintype "passive"))
      (node (ref "PAHC") (pin "2") (pinfunction "GND_2") (pintype "passive"))
      (node (ref "PAHL") (pin "2") (pinfunction "GND_2") (pintype "passive"))
      (node (ref "PAHX") (pin "2") (pinfunction "GND_2") (pintype "passive"))
      (node (ref "PAIK") (pin "2") (pinfunction "GND_2") (pintype "passive"))
      (node (ref "PAIM") (pin "2") (pinfunction "GND_2") (pintype "passive"))
      (node (ref "PAIN") (pin "2") (pinfunction "GND_2") (pintype "passive"))
      (node (ref "PAIW") (pin "2") (pinfunction "GND_2") (pintype "passive"))
      (node (ref "PAKK") (pin "2") (pinfunction "GND_2") (pintype "passive"))
      (node (ref "PAKP") (pin "2") (pinfunction "GND_2") (pintype "passive"))
      (node (ref "PAKU") (pin "2") (pinfunction "GND_2") (pintype "passive"))
      (node (ref "PAKV") (pin "2") (pinfunction "GND_2") (pintype "passive"))
      (node (ref "PALP") (pin "2") (pinfunction "GND_2") (pintype "passive"))
      (node (ref "PALU") (pin "2") (pinfunction "GND_2") (pintype "passive"))
      (node (ref "PAMC") (pin "2") (pinfunction "GND_2") (pintype "passive"))
      (node (ref "PAMH") (pin "2") (pinfunction "GND_2") (pintype "passive"))
      (node (ref "PAMK") (pin "2") (pinfunction "GND_2") (pintype "passive"))
      (node (ref "PAMO") (pin "2") (pinfunction "GND_2") (pintype "passive"))
      (node (ref "PANN") (pin "2") (pinfunction "GND_2") (pintype "passive"))
      (node (ref "PANU") (pin "2") (pinfunction "GND_2") (pintype "passive"))
      (node (ref "PANV") (pin "2") (pinfunction "GND_2") (pintype "passive"))
      (node (ref "PAOM") (pin "2") (pinfunction "GND_2") (pintype "passive"))
      (node (ref "PAOT") (pin "2") (pinfunction "GND_2") (pintype "passive"))
      (node (ref "PAPO") (pin "2") (pinfunction "GND_2") (pintype "passive"))
      (node (ref "PAPR") (pin "2") (pinfunction "GND_2") (pintype "passive"))
      (node (ref "PAQT") (pin "2") (pinfunction "GND_2") (pintype "passive"))
      (node (ref "PARS") (pin "2") (pinfunction "GND_2") (pintype "passive"))
      (node (ref "PARY") (pin "2") (pinfunction "GND_2") (pintype "passive"))
      (node (ref "PASH") (pin "2") (pinfunction "GND_2") (pintype "passive"))
      (node (ref "PASK") (pin "2") (pinfunction "GND_2") (pintype "passive"))
      (node (ref "PASM") (pin "2") (pinfunction "GND_2") (pintype "passive"))
      (node (ref "PATA") (pin "2") (pinfunction "GND_2") (pintype "passive"))
      (node (ref "PATC") (pin "2") (pinfunction "GND_2") (pintype "passive"))
      (node (ref "PATE") (pin "2") (pinfunction "GND_2") (pintype "passive"))
      (node (ref "PATL") (pin "2") (pinfunction "GND_2") (pintype "passive"))
      (node (ref "PATQ") (pin "2") (pinfunction "GND_2") (pintype "passive"))
      (node (ref "PAUN") (pin "2") (pinfunction "GND_2") (pintype "passive"))
      (node (ref "PAVA") (pin "2") (pinfunction "GND_2") (pintype "passive"))
      (node (ref "PAVL") (pin "2") (pinfunction "GND_2") (pintype "passive"))
      (node (ref "PAWM") (pin "2") (pinfunction "GND_2") (pintype "passive"))
      (node (ref "PAWN") (pin "2") (pinfunction "GND_2") (pintype "passive"))
      (node (ref "PFEL") (pin "2") (pinfunction "GND_2") (pintype "passive"))
      (node (ref "PFKT") (pin "2") (pinfunction "GND_2") (pintype "passive"))
      (node (ref "PFSH") (pin "2") (pinfunction "GND_2") (pintype "passive"))
      (node (ref "PPIZ") (pin "2") (pinfunction "GND_2") (pintype "passive"))
      (node (ref "Power / LED in1") (pin "3") (pinfunction "3_3") (pintype "passive"))
      (node (ref "Power / LED out1") (pin "3") (pinfunction "3_3") (pintype "passive"))
      (node (ref "Power Conn1") (pin "2") (pinfunction "NEG_2") (pintype "passive"))
      (node (ref "R1") (pin "1") (pinfunction "1_1") (pintype "passive"))
      (node (ref "R2") (pin "1") (pinfunction "1_1") (pintype "passive"))
      (node (ref "U1") (pin "1") (pinfunction "1nOE_1") (pintype "passive"))
      (node (ref "U1") (pin "7") (pinfunction "GND_7") (pintype "passive"))
      (node (ref "U2") (pin "1") (pinfunction "OE_1") (pintype "passive"))
      (node (ref "U2") (pin "7") (pinfunction "GND_7") (pintype "passive"))
      (node (ref "USB-C1") (pin "A1B12") (pinfunction "GND_A1B12") (pintype "passive"))
      (node (ref "USB-C1") (pin "B1A12") (pinfunction "GND_B1A12") (pintype "passive"))
      (node (ref "VFR") (pin "2") (pinfunction "GND_2") (pintype "passive"))
    )
    (net (code "3") (name "/LED in") (class "Default")
      (node (ref "PAGB") (pin "3") (pinfunction "DI_3") (pintype "passive"))
      (node (ref "U1") (pin "3") (pinfunction "1Y_3") (pintype "passive"))
      (node (ref "U2") (pin "3") (pinfunction "1Y_3") (pintype "passive"))
    )
    (net (code "4") (name "/Out") (class "Default")
      (node (ref "Connector Out1") (pin "3") (pinfunction "3_3") (pintype "passive"))
      (node (ref "Connector Out1") (pin "8") (pinfunction "8_8") (pintype "passive"))
      (node (ref "PASK") (pin "1") (pinfunction "DO_1") (pintype "passive"))
      (node (ref "Power / LED out1") (pin "2") (pinfunction "2_2") (pintype "passive"))
    )
    (net (code "5") (name "/VDD") (class "Default")
      (node (ref "C1") (pin "1") (pinfunction "1_1") (pintype "passive"))
      (node (ref "C10") (pin "1") (pinfunction "1_1") (pintype "passive"))
      (node (ref "C11") (pin "1") (pinfunction "1_1") (pintype "passive"))
      (node (ref "C12") (pin "1") (pinfunction "1_1") (pintype "passive"))
      (node (ref "C13") (pin "1") (pinfunction "1_1") (pintype "passive"))
      (node (ref "C14") (pin "1") (pinfunction "1_1") (pintype "passive"))
      (node (ref "C15") (pin "1") (pinfunction "1_1") (pintype "passive"))
      (node (ref "C16") (pin "1") (pinfunction "1_1") (pintype "passive"))
      (node (ref "C17") (pin "1") (pinfunction "1_1") (pintype "passive"))
      (node (ref "C18") (pin "1") (pinfunction "1_1") (pintype "passive"))
      (node (ref "C19") (pin "1") (pinfunction "1_1") (pintype "passive"))
      (node (ref "C2") (pin "1") (pinfunction "1_1") (pintype "passive"))
      (node (ref "C20") (pin "1") (pinfunction "1_1") (pintype "passive"))
      (node (ref "C21") (pin "1") (pinfunction "1_1") (pintype "passive"))
      (node (ref "C22") (pin "1") (pinfunction "1_1") (pintype "passive"))
      (node (ref "C23") (pin "1") (pinfunction "1_1") (pintype "passive"))
      (node (ref "C24") (pin "1") (pinfunction "1_1") (pintype "passive"))
      (node (ref "C25") (pin "1") (pinfunction "1_1") (pintype "passive"))
      (node (ref "C26") (pin "1") (pinfunction "1_1") (pintype "passive"))
      (node (ref "C27") (pin "1") (pinfunction "1_1") (pintype "passive"))
      (node (ref "C28") (pin "1") (pinfunction "1_1") (pintype "passive"))
      (node (ref "C29") (pin "1") (pinfunction "1_1") (pintype "passive"))
      (node (ref "C3") (pin "1") (pinfunction "1_1") (pintype "passive"))
      (node (ref "C30") (pin "1") (pinfunction "1_1") (pintype "passive"))
      (node (ref "C31") (pin "1") (pinfunction "1_1") (pintype "passive"))
      (node (ref "C32") (pin "1") (pinfunction "1_1") (pintype "passive"))
      (node (ref "C33") (pin "1") (pinfunction "1_1") (pintype "passive"))
      (node (ref "C34") (pin "1") (pinfunction "1_1") (pintype "passive"))
      (node (ref "C35") (pin "1") (pinfunction "1_1") (pintype "passive"))
      (node (ref "C36") (pin "1") (pinfunction "1_1") (pintype "passive"))
      (node (ref "C37") (pin "1") (pinfunction "1_1") (pintype "passive"))
      (node (ref "C38") (pin "1") (pinfunction "1_1") (pintype "passive"))
      (node (ref "C39") (pin "1") (pinfunction "1_1") (pintype "passive"))
      (node (ref "C4") (pin "1") (pinfunction "1_1") (pintype "passive"))
      (node (ref "C40") (pin "1") (pinfunction "1_1") (pintype "passive"))
      (node (ref "C41") (pin "1") (pinfunction "1_1") (pintype "passive"))
      (node (ref "C42") (pin "1") (pinfunction "1_1") (pintype "passive"))
      (node (ref "C43") (pin "1") (pinfunction "1_1") (pintype "passive"))
      (node (ref "C44") (pin "1") (pinfunction "1_1") (pintype "passive"))
      (node (ref "C45") (pin "1") (pinfunction "1_1") (pintype "passive"))
      (node (ref "C46") (pin "1") (pinfunction "1_1") (pintype "passive"))
      (node (ref "C47") (pin "1") (pinfunction "1_1") (pintype "passive"))
      (node (ref "C48") (pin "1") (pinfunction "1_1") (pintype "passive"))
      (node (ref "C49") (pin "1") (pinfunction "1_1") (pintype "passive"))
      (node (ref "C5") (pin "1") (pinfunction "1_1") (pintype "passive"))
      (node (ref "C50") (pin "1") (pinfunction "1_1") (pintype "passive"))
      (node (ref "C51") (pin "1") (pinfunction "1_1") (pintype "passive"))
      (node (ref "C52") (pin "1") (pinfunction "1_1") (pintype "passive"))
      (node (ref "C53") (pin "1") (pinfunction "1_1") (pintype "passive"))
      (node (ref "C54") (pin "1") (pinfunction "1_1") (pintype "passive"))
      (node (ref "C55") (pin "1") (pinfunction "1_1") (pintype "passive"))
      (node (ref "C56") (pin "1") (pinfunction "1_1") (pintype "passive"))
      (node (ref "C57") (pin "1") (pinfunction "1_1") (pintype "passive"))
      (node (ref "C58") (pin "1") (pinfunction "1_1") (pintype "passive"))
      (node (ref "C59") (pin "1") (pinfunction "1_1") (pintype "passive"))
      (node (ref "C6") (pin "1") (pinfunction "1_1") (pintype "passive"))
      (node (ref "C60") (pin "1") (pinfunction "1_1") (pintype "passive"))
      (node (ref "C61") (pin "1") (pinfunction "1_1") (pintype "passive"))
      (node (ref "C62") (pin "1") (pinfunction "1_1") (pintype "passive"))
      (node (ref "C63") (pin "1") (pinfunction "1_1") (pintype "passive"))
      (node (ref "C64") (pin "1") (pinfunction "1_1") (pintype "passive"))
      (node (ref "C65") (pin "1") (pinfunction "1_1") (pintype "passive"))
      (node (ref "C66") (pin "1") (pinfunction "1_1") (pintype "passive"))
      (node (ref "C67") (pin "1") (pinfunction "1_1") (pintype "passive"))
      (node (ref "C68") (pin "1") (pinfunction "1_1") (pintype "passive"))
      (node (ref "C69") (pin "1") (pinfunction "1_1") (pintype "passive"))
      (node (ref "C7") (pin "1") (pinfunction "1_1") (pintype "passive"))
      (node (ref "C8") (pin "1") (pinfunction "1_1") (pintype "passive"))
      (node (ref "C9") (pin "1") (pinfunction "1_1") (pintype "passive"))
      (node (ref "CPU Con1") (pin "1") (pinfunction "1_1") (pintype "passive"))
      (node (ref "CPU Con1") (pin "3") (pinfunction "3_3") (pintype "passive"))
      (node (ref "CPU-Con1") (pin "1") (pinfunction "1_1") (pintype "passive"))
      (node (ref "CPU-Con1") (pin "2") (pinfunction "2_2") (pintype "passive"))
      (node (ref "Connector In1") (pin "10") (pinfunction "10_10") (pintype "passive"))
      (node (ref "Connector In1") (pin "4") (pinfunction "4_4") (pintype "passive"))
      (node (ref "Connector In1") (pin "5") (pinfunction "5_5") (pintype "passive"))
      (node (ref "Connector In1") (pin "9") (pinfunction "9_9") (pintype "passive"))
      (node (ref "Connector Out1") (pin "10") (pinfunction "10_10") (pintype "passive"))
      (node (ref "Connector Out1") (pin "4") (pinfunction "4_4") (pintype "passive"))
      (node (ref "Connector Out1") (pin "5") (pinfunction "5_5") (pintype "passive"))
      (node (ref "Connector Out1") (pin "9") (pinfunction "9_9") (pintype "passive"))
      (node (ref "IFR") (pin "4") (pinfunction "VDD_4") (pintype "passive"))
      (node (ref "INVALID") (pin "4") (pinfunction "VDD_4") (pintype "passive"))
      (node (ref "LIFR") (pin "4") (pinfunction "VDD_4") (pintype "passive"))
      (node (ref "MVFR") (pin "4") (pinfunction "VDD_4") (pintype "passive"))
      (node (ref "PABL") (pin "4") (pinfunction "VDD_4") (pintype "passive"))
      (node (ref "PABR") (pin "4") (pinfunction "VDD_4") (pintype "passive"))
      (node (ref "PABT") (pin "4") (pinfunction "VDD_4") (pintype "passive"))
      (node (ref "PACM") (pin "4") (pinfunction "VDD_4") (pintype "passive"))
      (node (ref "PACX") (pin "4") (pinfunction "VDD_4") (pintype "passive"))
      (node (ref "PACZ") (pin "4") (pinfunction "VDD_4") (pintype "passive"))
      (node (ref "PADE") (pin "4") (pinfunction "VDD_4") (pintype "passive"))
      (node (ref "PADG") (pin "4") (pinfunction "VDD_4") (pintype "passive"))
      (node (ref "PADM") (pin "4") (pinfunction "VDD_4") (pintype "passive"))
      (node (ref "PAFA") (pin "4") (pinfunction "VDD_4") (pintype "passive"))
      (node (ref "PAFB") (pin "4") (pinfunction "VDD_4") (pintype "passive"))
      (node (ref "PAFM") (pin "4") (pinfunction "VDD_4") (pintype "passive"))
      (node (ref "PAFS") (pin "4") (pinfunction "VDD_4") (pintype "passive"))
      (node (ref "PAGA") (pin "4") (pinfunction "VDD_4") (pintype "passive"))
      (node (ref "PAGB") (pin "4") (pinfunction "VDD_4") (pintype "passive"))
      (node (ref "PAGH") (pin "4") (pinfunction "VDD_4") (pintype "passive"))
      (node (ref "PAGL") (pin "4") (pinfunction "VDD_4") (pintype "passive"))
      (node (ref "PAHC") (pin "4") (pinfunction "VDD_4") (pintype "passive"))
      (node (ref "PAHL") (pin "4") (pinfunction "VDD_4") (pintype "passive"))
      (node (ref "PAHX") (pin "4") (pinfunction "VDD_4") (pintype "passive"))
      (node (ref "PAIK") (pin "4") (pinfunction "VDD_4") (pintype "passive"))
      (node (ref "PAIM") (pin "4") (pinfunction "VDD_4") (pintype "passive"))
      (node (ref "PAIN") (pin "4") (pinfunction "VDD_4") (pintype "passive"))
      (node (ref "PAIW") (pin "4") (pinfunction "VDD_4") (pintype "passive"))
      (node (ref "PAKK") (pin "4") (pinfunction "VDD_4") (pintype "passive"))
      (node (ref "PAKP") (pin "4") (pinfunction "VDD_4") (pintype "passive"))
      (node (ref "PAKU") (pin "4") (pinfunction "VDD_4") (pintype "passive"))
      (node (ref "PAKV") (pin "4") (pinfunction "VDD_4") (pintype "passive"))
      (node (ref "PALP") (pin "4") (pinfunction "VDD_4") (pintype "passive"))
      (node (ref "PALU") (pin "4") (pinfunction "VDD_4") (pintype "passive"))
      (node (ref "PAMC") (pin "4") (pinfunction "VDD_4") (pintype "passive"))
      (node (ref "PAMH") (pin "4") (pinfunction "VDD_4") (pintype "passive"))
      (node (ref "PAMK") (pin "4") (pinfunction "VDD_4") (pintype "passive"))
      (node (ref "PAMO") (pin "4") (pinfunction "VDD_4") (pintype "passive"))
      (node (ref "PANN") (pin "4") (pinfunction "VDD_4") (pintype "passive"))
      (node (ref "PANU") (pin "4") (pinfunction "VDD_4") (pintype "passive"))
      (node (ref "PANV") (pin "4") (pinfunction "VDD_4") (pintype "passive"))
      (node (ref "PAOM") (pin "4") (pinfunction "VDD_4") (pintype "passive"))
      (node (ref "PAOT") (pin "4") (pinfunction "VDD_4") (pintype "passive"))
      (node (ref "PAPO") (pin "4") (pinfunction "VDD_4") (pintype "passive"))
      (node (ref "PAPR") (pin "4") (pinfunction "VDD_4") (pintype "passive"))
      (node (ref "PAQT") (pin "4") (pinfunction "VDD_4") (pintype "passive"))
      (node (ref "PARS") (pin "4") (pinfunction "VDD_4") (pintype "passive"))
      (node (ref "PARY") (pin "4") (pinfunction "VDD_4") (pintype "passive"))
      (node (ref "PASH") (pin "4") (pinfunction "VDD_4") (pintype "passive"))
      (node (ref "PASK") (pin "4") (pinfunction "VDD_4") (pintype "passive"))
      (node (ref "PASM") (pin "4") (pinfunction "VDD_4") (pintype "passive"))
      (node (ref "PATA") (pin "4") (pinfunction "VDD_4") (pintype "passive"))
      (node (ref "PATC") (pin "4") (pinfunction "VDD_4") (pintype "passive"))
      (node (ref "PATE") (pin "4") (pinfunction "VDD_4") (pintype "passive"))
      (node (ref "PATL") (pin "4") (pinfunction "VDD_4") (pintype "passive"))
      (node (ref "PATQ") (pin "4") (pinfunction "VDD_4") (pintype "passive"))
      (node (ref "PAUN") (pin "4") (pinfunction "VDD_4") (pintype "passive"))
      (node (ref "PAVA") (pin "4") (pinfunction "VDD_4") (pintype "passive"))
      (node (ref "PAVL") (pin "4") (pinfunction "VDD_4") (pintype "passive"))
      (node (ref "PAWM") (pin "4") (pinfunction "VDD_4") (pintype "passive"))
      (node (ref "PAWN") (pin "4") (pinfunction "VDD_4") (pintype "passive"))
      (node (ref "PFEL") (pin "4") (pinfunction "VDD_4") (pintype "passive"))
      (node (ref "PFKT") (pin "4") (pinfunction "VDD_4") (pintype "passive"))
      (node (ref "PFSH") (pin "4") (pinfunction "VDD_4") (pintype "passive"))
      (node (ref "PPIZ") (pin "4") (pinfunction "VDD_4") (pintype "passive"))
      (node (ref "Power / LED in1") (pin "1") (pinfunction "1_1") (pintype "passive"))
      (node (ref "Power / LED out1") (pin "1") (pinfunction "1_1") (pintype "passive"))
      (node (ref "Power Conn1") (pin "1") (pinfunction "POS_1") (pintype "passive"))
      (node (ref "U1") (pin "14") (pinfunction "VCC_14") (pintype "passive"))
      (node (ref "U2") (pin "14") (pinfunction "Vcc_14") (pintype "passive"))
      (node (ref "USB-C1") (pin "A4B9") (pinfunction "VBUS_A4B9") (pintype "passive"))
      (node (ref "USB-C1") (pin "B4A9") (pinfunction "VBUS_B4A9") (pintype "passive"))
      (node (ref "VFR") (pin "4") (pinfunction "VDD_4") (pintype "passive"))
    )
    (net (code "6") (name "Net-(IFR-DI)") (class "Default")
      (node (ref "IFR") (pin "3") (pinfunction "DI_3") (pintype "passive"))
      (node (ref "LIFR") (pin "1") (pinfunction "DO_1") (pintype "passive"))
    )
    (net (code "7") (name "Net-(IFR-DO)") (class "Default")
      (node (ref "IFR") (pin "1") (pinfunction "DO_1") (pintype "passive"))
      (node (ref "MVFR") (pin "3") (pinfunction "DI_3") (pintype "passive"))
    )
    (net (code "8") (name "Net-(INVALID-DI)") (class "Default")
      (node (ref "INVALID") (pin "3") (pinfunction "DI_3") (pintype "passive"))
      (node (ref "PAIW") (pin "1") (pinfunction "DO_1") (pintype "passive"))
    )
    (net (code "9") (name "Net-(INVALID-DO)") (class "Default")
      (node (ref "INVALID") (pin "1") (pinfunction "DO_1") (pintype "passive"))
      (node (ref "LIFR") (pin "3") (pinfunction "DI_3") (pintype "passive"))
    )
    (net (code "10") (name "Net-(MVFR-DO)") (class "Default")
      (node (ref "MVFR") (pin "1") (pinfunction "DO_1") (pintype "passive"))
      (node (ref "VFR") (pin "3") (pinfunction "DI_3") (pintype "passive"))
    )
    (net (code "11") (name "Net-(PABL-DI)") (class "Default")
      (node (ref "PABL") (pin "3") (pinfunction "DI_3") (pintype "passive"))
      (node (ref "PAKK") (pin "1") (pinfunction "DO_1") (pintype "passive"))
    )
    (net (code "12") (name "Net-(PABL-DO)") (class "Default")
      (node (ref "PABL") (pin "1") (pinfunction "DO_1") (pintype "passive"))
      (node (ref "PASK") (pin "3") (pinfunction "DI_3") (pintype "passive"))
    )
    (net (code "13") (name "Net-(PABR-DI)") (class "Default")
      (node (ref "PABR") (pin "3") (pinfunction "DI_3") (pintype "passive"))
      (node (ref "VFR") (pin "1") (pinfunction "DO_1") (pintype "passive"))
    )
    (net (code "14") (name "Net-(PABR-DO)") (class "Default")
      (node (ref "PABR") (pin "1") (pinfunction "DO_1") (pintype "passive"))
      (node (ref "PALP") (pin "3") (pinfunction "DI_3") (pintype "passive"))
    )
    (net (code "15") (name "Net-(PABT-DI)") (class "Default")
      (node (ref "PABT") (pin "3") (pinfunction "DI_3") (pintype "passive"))
      (node (ref "PADG") (pin "1") (pinfunction "DO_1") (pintype "passive"))
    )
    (net (code "16") (name "Net-(PABT-DO)") (class "Default")
      (node (ref "PABT") (pin "1") (pinfunction "DO_1") (pintype "passive"))
      (node (ref "PAIM") (pin "3") (pinfunction "DI_3") (pintype "passive"))
    )
    (net (code "17") (name "Net-(PACM-DI)") (class "Default")
      (node (ref "PACM") (pin "3") (pinfunction "DI_3") (pintype "passive"))
      (node (ref "PAVA") (pin "1") (pinfunction "DO_1") (pintype "passive"))
    )
    (net (code "18") (name "Net-(PACM-DO)") (class "Default")
      (node (ref "PACM") (pin "1") (pinfunction "DO_1") (pintype "passive"))
      (node (ref "PACZ") (pin "3") (pinfunction "DI_3") (pintype "passive"))
    )
    (net (code "19") (name "Net-(PACX-DI)") (class "Default")
      (node (ref "PACX") (pin "3") (pinfunction "DI_3") (pintype "passive"))
      (node (ref "PAKU") (pin "1") (pinfunction "DO_1") (pintype "passive"))
    )
    (net (code "20") (name "Net-(PACX-DO)") (class "Default")
      (node (ref "PACX") (pin "1") (pinfunction "DO_1") (pintype "passive"))
      (node (ref "PAFA") (pin "3") (pinfunction "DI_3") (pintype "passive"))
    )
    (net (code "21") (name "Net-(PACZ-DO)") (class "Default")
      (node (ref "PACZ") (pin "1") (pinfunction "DO_1") (pintype "passive"))
      (node (ref "PAIW") (pin "3") (pinfunction "DI_3") (pintype "passive"))
    )
    (net (code "22") (name "Net-(PADE-DI)") (class "Default")
      (node (ref "PADE") (pin "3") (pinfunction "DI_3") (pintype "passive"))
      (node (ref "PFEL") (pin "1") (pinfunction "DO_1") (pintype "passive"))
    )
    (net (code "23") (name "Net-(PADE-DO)") (class "Default")
      (node (ref "PADE") (pin "1") (pinfunction "DO_1") (pintype "passive"))
      (node (ref "PAOT") (pin "3") (pinfunction "DI_3") (pintype "passive"))
    )
    (net (code "24") (name "Net-(PADG-DI)") (class "Default")
      (node (ref "PADG") (pin "3") (pinfunction "DI_3") (pintype "passive"))
      (node (ref "PAVL") (pin "1") (pinfunction "DO_1") (pintype "passive"))
    )
    (net (code "25") (name "Net-(PADM-DI)") (class "Default")
      (node (ref "PADM") (pin "3") (pinfunction "DI_3") (pintype "passive"))
      (node (ref "PARS") (pin "1") (pinfunction "DO_1") (pintype "passive"))
    )
    (net (code "26") (name "Net-(PADM-DO)") (class "Default")
      (node (ref "PADM") (pin "1") (pinfunction "DO_1") (pintype "passive"))
      (node (ref "PASM") (pin "3") (pinfunction "DI_3") (pintype "passive"))
    )
    (net (code "27") (name "Net-(PAFA-DO)") (class "Default")
      (node (ref "PAFA") (pin "1") (pinfunction "DO_1") (pintype "passive"))
      (node (ref "PANN") (pin "3") (pinfunction "DI_3") (pintype "passive"))
    )
    (net (code "28") (name "Net-(PAFB-DI)") (class "Default")
      (node (ref "PAFB") (pin "3") (pinfunction "DI_3") (pintype "passive"))
      (node (ref "PAGB") (pin "1") (pinfunction "DO_1") (pintype "passive"))
    )
    (net (code "29") (name "Net-(PAFB-DO)") (class "Default")
      (node (ref "PAFB") (pin "1") (pinfunction "DO_1") (pintype "passive"))
      (node (ref "PAIN") (pin "3") (pinfunction "DI_3") (pintype "passive"))
    )
    (net (code "30") (name "Net-(PAFM-DI)") (class "Default")
      (node (ref "PAFM") (pin "3") (pinfunction "DI_3") (pintype "passive"))
      (node (ref "PAIK") (pin "1") (pinfunction "DO_1") (pintype "passive"))
    )
    (net (code "31") (name "Net-(PAFM-DO)") (class "Default")
      (node (ref "PAFM") (pin "1") (pinfunction "DO_1") (pintype "passive"))
      (node (ref "PAGH") (pin "3") (pinfunction "DI_3") (pintype "passive"))
    )
    (net (code "32") (name "Net-(PAFS-DI)") (class "Default")
      (node (ref "PAFS") (pin "3") (pinfunction "DI_3") (pintype "passive"))
      (node (ref "PAIN") (pin "1") (pinfunction "DO_1") (pintype "passive"))
    )
    (net (code "33") (name "Net-(PAFS-DO)") (class "Default")
      (node (ref "PAFS") (pin "1") (pinfunction "DO_1") (pintype "passive"))
      (node (ref "PAMC") (pin "3") (pinfunction "DI_3") (pintype "passive"))
    )
    (net (code "34") (name "Net-(PAGA-DI)") (class "Default")
      (node (ref "PAGA") (pin "3") (pinfunction "DI_3") (pintype "passive"))
      (node (ref "PARY") (pin "1") (pinfunction "DO_1") (pintype "passive"))
    )
    (net (code "35") (name "Net-(PAGA-DO)") (class "Default")
      (node (ref "PAGA") (pin "1") (pinfunction "DO_1") (pintype "passive"))
      (node (ref "PAKV") (pin "3") (pinfunction "DI_3") (pintype "passive"))
    )
    (net (code "36") (name "Net-(PAGH-DO)") (class "Default")
      (node (ref "PAGH") (pin "1") (pinfunction "DO_1") (pintype "passive"))
      (node (ref "PAHL") (pin "3") (pinfunction "DI_3") (pintype "passive"))
    )
    (net (code "37") (name "Net-(PAGL-DI)") (class "Default")
      (node (ref "PAGL") (pin "3") (pinfunction "DI_3") (pintype "passive"))
      (node (ref "PAUN") (pin "1") (pinfunction "DO_1") (pintype "passive"))
    )
    (net (code "38") (name "Net-(PAGL-DO)") (class "Default")
      (node (ref "PAGL") (pin "1") (pinfunction "DO_1") (pintype "passive"))
      (node (ref "PAWM") (pin "3") (pinfunction "DI_3") (pintype "passive"))
    )
    (net (code "39") (name "Net-(PAHC-DI)") (class "Default")
      (node (ref "PAHC") (pin "3") (pinfunction "DI_3") (pintype "passive"))
      (node (ref "PATL") (pin "1") (pinfunction "DO_1") (pintype "passive"))
    )
    (net (code "40") (name "Net-(PAHC-DO)") (class "Default")
      (node (ref "PAHC") (pin "1") (pinfunction "DO_1") (pintype "passive"))
      (node (ref "PARS") (pin "3") (pinfunction "DI_3") (pintype "passive"))
    )
    (net (code "41") (name "Net-(PAHL-DO)") (class "Default")
      (node (ref "PAHL") (pin "1") (pinfunction "DO_1") (pintype "passive"))
      (node (ref "PAKK") (pin "3") (pinfunction "DI_3") (pintype "passive"))
    )
    (net (code "42") (name "Net-(PAHX-DI)") (class "Default")
      (node (ref "PAHX") (pin "3") (pinfunction "DI_3") (pintype "passive"))
      (node (ref "PAMH") (pin "1") (pinfunction "DO_1") (pintype "passive"))
    )
    (net (code "43") (name "Net-(PAHX-DO)") (class "Default")
      (node (ref "PAHX") (pin "1") (pinfunction "DO_1") (pintype "passive"))
      (node (ref "PANV") (pin "3") (pinfunction "DI_3") (pintype "passive"))
    )
    (net (code "44") (name "Net-(PAIK-DI)") (class "Default")
      (node (ref "PAIK") (pin "3") (pinfunction "DI_3") (pintype "passive"))
      (node (ref "PAWN") (pin "1") (pinfunction "DO_1") (pintype "passive"))
    )
    (net (code "45") (name "Net-(PAIM-DO)") (class "Default")
      (node (ref "PAIM") (pin "1") (pinfunction "DO_1") (pintype "passive"))
      (node (ref "PANU") (pin "3") (pinfunction "DI_3") (pintype "passive"))
    )
    (net (code "46") (name "Net-(PAKP-DI)") (class "Default")
      (node (ref "PAKP") (pin "3") (pinfunction "DI_3") (pintype "passive"))
      (node (ref "PAQT") (pin "1") (pinfunction "DO_1") (pintype "passive"))
    )
    (net (code "47") (name "Net-(PAKP-DO)") (class "Default")
      (node (ref "PAKP") (pin "1") (pinfunction "DO_1") (pintype "passive"))
      (node (ref "PAPR") (pin "3") (pinfunction "DI_3") (pintype "passive"))
    )
    (net (code "48") (name "Net-(PAKU-DI)") (class "Default")
      (node (ref "PAKU") (pin "3") (pinfunction "DI_3") (pintype "passive"))
      (node (ref "PALP") (pin "1") (pinfunction "DO_1") (pintype "passive"))
    )
    (net (code "49") (name "Net-(PAKV-DO)") (class "Default")
      (node (ref "PAKV") (pin "1") (pinfunction "DO_1") (pintype "passive"))
      (node (ref "PAUN") (pin "3") (pinfunction "DI_3") (pintype "passive"))
    )
    (net (code "50") (name "Net-(PALU-DI)") (class "Default")
      (node (ref "PALU") (pin "3") (pinfunction "DI_3") (pintype "passive"))
      (node (ref "PAPO") (pin "1") (pinfunction "DO_1") (pintype "passive"))
    )
    (net (code "51") (name "Net-(PALU-DO)") (class "Default")
      (node (ref "PALU") (pin "1") (pinfunction "DO_1") (pintype "passive"))
      (node (ref "PPIZ") (pin "3") (pinfunction "DI_3") (pintype "passive"))
    )
    (net (code "52") (name "Net-(PAMC-DO)") (class "Default")
      (node (ref "PAMC") (pin "1") (pinfunction "DO_1") (pintype "passive"))
      (node (ref "PATL") (pin "3") (pinfunction "DI_3") (pintype "passive"))
    )
    (net (code "53") (name "Net-(PAMH-DI)") (class "Default")
      (node (ref "PAMH") (pin "3") (pinfunction "DI_3") (pintype "passive"))
      (node (ref "PANN") (pin "1") (pinfunction "DO_1") (pintype "passive"))
    )
    (net (code "54") (name "Net-(PAMK-DI)") (class "Default")
      (node (ref "PAMK") (pin "3") (pinfunction "DI_3") (pintype "passive"))
      (node (ref "PANV") (pin "1") (pinfunction "DO_1") (pintype "passive"))
    )
    (net (code "55") (name "Net-(PAMK-DO)") (class "Default")
      (node (ref "PAMK") (pin "1") (pinfunction "DO_1") (pintype "passive"))
      (node (ref "PAOM") (pin "3") (pinfunction "DI_3") (pintype "passive"))
    )
    (net (code "56") (name "Net-(PAMO-DI)") (class "Default")
      (node (ref "PAMO") (pin "3") (pinfunction "DI_3") (pintype "passive"))
      (node (ref "PASM") (pin "1") (pinfunction "DO_1") (pintype "passive"))
    )
    (net (code "57") (name "Net-(PAMO-DO)") (class "Default")
      (node (ref "PAMO") (pin "1") (pinfunction "DO_1") (pintype "passive"))
      (node (ref "PAVA") (pin "3") (pinfunction "DI_3") (pintype "passive"))
    )
    (net (code "58") (name "Net-(PANU-DO)") (class "Default")
      (node (ref "PANU") (pin "1") (pinfunction "DO_1") (pintype "passive"))
      (node (ref "PFSH") (pin "3") (pinfunction "DI_3") (pintype "passive"))
    )
    (net (code "59") (name "Net-(PAOM-DO)") (class "Default")
      (node (ref "PAOM") (pin "1") (pinfunction "DO_1") (pintype "passive"))
      (node (ref "PATC") (pin "3") (pinfunction "DI_3") (pintype "passive"))
    )
    (net (code "60") (name "Net-(PAOT-DO)") (class "Default")
      (node (ref "PAOT") (pin "1") (pinfunction "DO_1") (pintype "passive"))
      (node (ref "PAWN") (pin "3") (pinfunction "DI_3") (pintype "passive"))
    )
    (net (code "61") (name "Net-(PAPO-DI)") (class "Default")
      (node (ref "PAPO") (pin "3") (pinfunction "DI_3") (pintype "passive"))
      (node (ref "PATC") (pin "1") (pinfunction "DO_1") (pintype "passive"))
    )
    (net (code "62") (name "Net-(PAPR-DO)") (class "Default")
      (node (ref "PAPR") (pin "1") (pinfunction "DO_1") (pintype "passive"))
      (node (ref "PATA") (pin "3") (pinfunction "DI_3") (pintype "passive"))
    )
    (net (code "63") (name "Net-(PAQT-DI)") (class "Default")
      (node (ref "PAQT") (pin "3") (pinfunction "DI_3") (pintype "passive"))
      (node (ref "PATQ") (pin "1") (pinfunction "DO_1") (pintype "passive"))
    )
    (net (code "64") (name "Net-(PARY-DI)") (class "Default")
      (node (ref "PARY") (pin "3") (pinfunction "DI_3") (pintype "passive"))
      (node (ref "PATA") (pin "1") (pinfunction "DO_1") (pintype "passive"))
    )
    (net (code "65") (name "Net-(PASH-DI)") (class "Default")
      (node (ref "PASH") (pin "3") (pinfunction "DI_3") (pintype "passive"))
      (node (ref "PFKT") (pin "1") (pinfunction "DO_1") (pintype "passive"))
    )
    (net (code "66") (name "Net-(PASH-DO)") (class "Default")
      (node (ref "PASH") (pin "1") (pinfunction "DO_1") (pintype "passive"))
      (node (ref "PAVL") (pin "3") (pinfunction "DI_3") (pintype "passive"))
    )
    (net (code "67") (name "Net-(PATE-DI)") (class "Default")
      (node (ref "PATE") (pin "3") (pinfunction "DI_3") (pintype "passive"))
      (node (ref "PAWM") (pin "1") (pinfunction "DO_1") (pintype "passive"))
    )
    (net (code "68") (name "Net-(PATE-DO)") (class "Default")
      (node (ref "PATE") (pin "1") (pinfunction "DO_1") (pintype "passive"))
      (node (ref "PFKT") (pin "3") (pinfunction "DI_3") (pintype "passive"))
    )
    (net (code "69") (name "Net-(PATQ-DI)") (class "Default")
      (node (ref "PATQ") (pin "3") (pinfunction "DI_3") (pintype "passive"))
      (node (ref "PPIZ") (pin "1") (pinfunction "DO_1") (pintype "passive"))
    )
    (net (code "70") (name "Net-(PFEL-DI)") (class "Default")
      (node (ref "PFEL") (pin "3") (pinfunction "DI_3") (pintype "passive"))
      (node (ref "PFSH") (pin "1") (pinfunction "DO_1") (pintype "passive"))
    )
    (net (code "71") (name "Net-(USB-C1-CC1)") (class "Default")
      (node (ref "R1") (pin "2") (pinfunction "2_2") (pintype "passive"))
      (node (ref "USB-C1") (pin "A5") (pinfunction "CC1_A5") (pintype "passive"))
    )
    (net (code "72") (name "Net-(USB-C1-CC2)") (class "Default")
      (node (ref "R2") (pin "2") (pinfunction "2_2") (pintype "passive"))
      (node (ref "USB-C1") (pin "B5") (pinfunction "CC2_B5") (pintype "passive"))
    )
    (net (code "73") (name "unconnected-(CPU Con1-Pad2)") (class "Default")
      (node (ref "CPU Con1") (pin "2") (pinfunction "2_2") (pintype "passive"))
    )
    (net (code "74") (name "unconnected-(CPU Con1-Pad4)") (class "Default")
      (node (ref "CPU Con1") (pin "4") (pinfunction "4_4") (pintype "passive"))
    )
    (net (code "75") (name "unconnected-(CPU Con1-Pad6)") (class "Default")
      (node (ref "CPU Con1") (pin "6") (pinfunction "6_6") (pintype "passive"))
    )
    (net (code "76") (name "unconnected-(CPU Con1-Pad7)") (class "Default")
      (node (ref "CPU Con1") (pin "7") (pinfunction "7_7") (pintype "passive"))
    )
    (net (code "77") (name "unconnected-(CPU Con1-Pad8)") (class "Default")
      (node (ref "CPU Con1") (pin "8") (pinfunction "8_8") (pintype "passive"))
    )
    (net (code "78") (name "unconnected-(CPU Con1-Pad9)") (class "Default")
      (node (ref "CPU Con1") (pin "9") (pinfunction "9_9") (pintype "passive"))
    )
    (net (code "79") (name "unconnected-(CPU Con1-Pad12)") (class "Default")
      (node (ref "CPU Con1") (pin "12") (pinfunction "12_12") (pintype "passive"))
    )
    (net (code "80") (name "unconnected-(CPU Con1-Pad14)") (class "Default")
      (node (ref "CPU Con1") (pin "14") (pinfunction "14_14") (pintype "passive"))
    )
    (net (code "81") (name "unconnected-(CPU Con1-Pad15)") (class "Default")
      (node (ref "CPU Con1") (pin "15") (pinfunction "15_15") (pintype "passive"))
    )
    (net (code "82") (name "unconnected-(CPU Con1-Pad16)") (class "Default")
      (node (ref "CPU Con1") (pin "16") (pinfunction "16_16") (pintype "passive"))
    )
    (net (code "83") (name "unconnected-(CPU Con1-Pad17)") (class "Default")
      (node (ref "CPU Con1") (pin "17") (pinfunction "17_17") (pintype "passive"))
    )
    (net (code "84") (name "unconnected-(CPU Con1-Pad18)") (class "Default")
      (node (ref "CPU Con1") (pin "18") (pinfunction "18_18") (pintype "passive"))
    )
    (net (code "85") (name "unconnected-(CPU Con1-Pad20)") (class "Default")
      (node (ref "CPU Con1") (pin "20") (pinfunction "20_20") (pintype "passive"))
    )
    (net (code "86") (name "unconnected-(CPU Con1-Pad21)") (class "Default")
      (node (ref "CPU Con1") (pin "21") (pinfunction "21_21") (pintype "passive"))
    )
    (net (code "87") (name "unconnected-(CPU Con1-Pad22)") (class "Default")
      (node (ref "CPU Con1") (pin "22") (pinfunction "22_22") (pintype "passive"))
    )
    (net (code "88") (name "unconnected-(CPU Con1-Pad23)") (class "Default")
      (node (ref "CPU Con1") (pin "23") (pinfunction "23_23") (pintype "passive"))
    )
    (net (code "89") (name "unconnected-(CPU Con1-Pad24)") (class "Default")
      (node (ref "CPU Con1") (pin "24") (pinfunction "24_24") (pintype "passive"))
    )
    (net (code "90") (name "unconnected-(CPU Con1-Pad25)") (class "Default")
      (node (ref "CPU Con1") (pin "25") (pinfunction "25_25") (pintype "passive"))
    )
    (net (code "91") (name "unconnected-(CPU Con1-Pad27)") (class "Default")
      (node (ref "CPU Con1") (pin "27") (pinfunction "27_27") (pintype "passive"))
    )
    (net (code "92") (name "unconnected-(CPU Con1-Pad28)") (class "Default")
      (node (ref "CPU Con1") (pin "28") (pinfunction "28_28") (pintype "passive"))
    )
    (net (code "93") (name "unconnected-(CPU Con1-Pad30)") (class "Default")
      (node (ref "CPU Con1") (pin "30") (pinfunction "30_30") (pintype "passive"))
    )
    (net (code "94") (name "unconnected-(CPU Con1-Pad31)") (class "Default")
      (node (ref "CPU Con1") (pin "31") (pinfunction "31_31") (pintype "passive"))
    )
    (net (code "95") (name "unconnected-(CPU Con1-Pad32)") (class "Default")
      (node (ref "CPU Con1") (pin "32") (pinfunction "32_32") (pintype "passive"))
    )
    (net (code "96") (name "unconnected-(CPU Con1-Pad34)") (class "Default")
      (node (ref "CPU Con1") (pin "34") (pinfunction "34_34") (pintype "passive"))
    )
    (net (code "97") (name "unconnected-(CPU Con1-Pad35)") (class "Default")
      (node (ref "CPU Con1") (pin "35") (pinfunction "35_35") (pintype "passive"))
    )
    (net (code "98") (name "unconnected-(CPU Con1-Pad36)") (class "Default")
      (node (ref "CPU Con1") (pin "36") (pinfunction "36_36") (pintype "passive"))
    )
    (net (code "99") (name "unconnected-(CPU Con1-Pad37)") (class "Default")
      (node (ref "CPU Con1") (pin "37") (pinfunction "37_37") (pintype "passive"))
    )
    (net (code "100") (name "unconnected-(CPU Con1-Pad38)") (class "Default")
      (node (ref "CPU Con1") (pin "38") (pinfunction "38_38") (pintype "passive"))
    )
    (net (code "101") (name "unconnected-(CPU Con1-Pad39)") (class "Default")
      (node (ref "CPU Con1") (pin "39") (pinfunction "39_39") (pintype "passive"))
    )
    (net (code "102") (name "unconnected-(CPU-Con1-Pad4)") (class "Default")
      (node (ref "CPU-Con1") (pin "4") (pinfunction "4_4") (pintype "passive"))
    )
    (net (code "103") (name "unconnected-(CPU-Con1-Pad5)") (class "Default")
      (node (ref "CPU-Con1") (pin "5") (pinfunction "5_5") (pintype "passive"))
    )
    (net (code "104") (name "unconnected-(CPU-Con1-Pad8)") (class "Default")
      (node (ref "CPU-Con1") (pin "8") (pinfunction "8_8") (pintype "passive"))
    )
    (net (code "105") (name "unconnected-(CPU-Con1-Pad9)") (class "Default")
      (node (ref "CPU-Con1") (pin "9") (pinfunction "9_9") (pintype "passive"))
    )
    (net (code "106") (name "unconnected-(CPU-Con1-Pad11)") (class "Default")
      (node (ref "CPU-Con1") (pin "11") (pinfunction "11_11") (pintype "passive"))
    )
    (net (code "107") (name "unconnected-(CPU-Con1-Pad12)") (class "Default")
      (node (ref "CPU-Con1") (pin "12") (pinfunction "12_12") (pintype "passive"))
    )
    (net (code "108") (name "unconnected-(CPU-Con1-Pad13)") (class "Default")
      (node (ref "CPU-Con1") (pin "13") (pinfunction "13_13") (pintype "passive"))
    )
    (net (code "109") (name "unconnected-(CPU-Con1-Pad14)") (class "Default")
      (node (ref "CPU-Con1") (pin "14") (pinfunction "14_14") (pintype "passive"))
    )
    (net (code "110") (name "unconnected-(CPU-Con1-Pad16)") (class "Default")
      (node (ref "CPU-Con1") (pin "16") (pinfunction "16_16") (pintype "passive"))
    )
    (net (code "111") (name "unconnected-(CPU-Con1-Pad18)") (class "Default")
      (node (ref "CPU-Con1") (pin "18") (pinfunction "18_18") (pintype "passive"))
    )
    (net (code "112") (name "unconnected-(CPU-Con1-Pad19)") (class "Default")
      (node (ref "CPU-Con1") (pin "19") (pinfunction "19_19") (pintype "passive"))
    )
    (net (code "113") (name "unconnected-(CPU-Con1-Pad20)") (class "Default")
      (node (ref "CPU-Con1") (pin "20") (pinfunction "20_20") (pintype "passive"))
    )
    (net (code "114") (name "unconnected-(CPU-Con1-Pad21)") (class "Default")
      (node (ref "CPU-Con1") (pin "21") (pinfunction "21_21") (pintype "passive"))
    )
    (net (code "115") (name "unconnected-(CPU-Con1-Pad22)") (class "Default")
      (node (ref "CPU-Con1") (pin "22") (pinfunction "22_22") (pintype "passive"))
    )
    (net (code "116") (name "unconnected-(CPU-Con1-Pad23)") (class "Default")
      (node (ref "CPU-Con1") (pin "23") (pinfunction "23_23") (pintype "passive"))
    )
    (net (code "117") (name "unconnected-(CPU-Con1-Pad24)") (class "Default")
      (node (ref "CPU-Con1") (pin "24") (pinfunction "24_24") (pintype "passive"))
    )
    (net (code "118") (name "unconnected-(CPU-Con1-Pad26)") (class "Default")
      (node (ref "CPU-Con1") (pin "26") (pinfunction "26_26") (pintype "passive"))
    )
    (net (code "119") (name "unconnected-(CPU-Con1-Pad27)") (class "Default")
      (node (ref "CPU-Con1") (pin "27") (pinfunction "27_27") (pintype "passive"))
    )
    (net (code "120") (name "unconnected-(CPU-Con1-Pad28)") (class "Default")
      (node (ref "CPU-Con1") (pin "28") (pinfunction "28_28") (pintype "passive"))
    )
    (net (code "121") (name "unconnected-(CPU-Con1-Pad29)") (class "Default")
      (node (ref "CPU-Con1") (pin "29") (pinfunction "29_29") (pintype "passive"))
    )
    (net (code "122") (name "unconnected-(CPU-Con1-Pad30)") (class "Default")
      (node (ref "CPU-Con1") (pin "30") (pinfunction "30_30") (pintype "passive"))
    )
    (net (code "123") (name "unconnected-(CPU-Con1-Pad31)") (class "Default")
      (node (ref "CPU-Con1") (pin "31") (pinfunction "31_31") (pintype "passive"))
    )
    (net (code "124") (name "unconnected-(CPU-Con1-Pad32)") (class "Default")
      (node (ref "CPU-Con1") (pin "32") (pinfunction "32_32") (pintype "passive"))
    )
    (net (code "125") (name "unconnected-(CPU-Con1-Pad34)") (class "Default")
      (node (ref "CPU-Con1") (pin "34") (pinfunction "34_34") (pintype "passive"))
    )
    (net (code "126") (name "unconnected-(CPU-Con1-Pad35)") (class "Default")
      (node (ref "CPU-Con1") (pin "35") (pinfunction "35_35") (pintype "passive"))
    )
    (net (code "127") (name "unconnected-(CPU-Con1-Pad36)") (class "Default")
      (node (ref "CPU-Con1") (pin "36") (pinfunction "36_36") (pintype "passive"))
    )
    (net (code "128") (name "unconnected-(CPU-Con1-Pad37)") (class "Default")
      (node (ref "CPU-Con1") (pin "37") (pinfunction "37_37") (pintype "passive"))
    )
    (net (code "129") (name "unconnected-(CPU-Con1-Pad38)") (class "Default")
      (node (ref "CPU-Con1") (pin "38") (pinfunction "38_38") (pintype "passive"))
    )
    (net (code "130") (name "unconnected-(CPU-Con1-Pad39)") (class "Default")
      (node (ref "CPU-Con1") (pin "39") (pinfunction "39_39") (pintype "passive"))
    )
    (net (code "131") (name "unconnected-(U1-2A-Pad5)") (class "Default")
      (node (ref "U1") (pin "5") (pinfunction "2A_5") (pintype "passive"))
    )
    (net (code "132") (name "unconnected-(U1-2Y-Pad6)") (class "Default")
      (node (ref "U1") (pin "6") (pinfunction "2Y_6") (pintype "passive"))
    )
    (net (code "133") (name "unconnected-(U1-2nOE-Pad4)") (class "Default")
      (node (ref "U1") (pin "4") (pinfunction "2nOE_4") (pintype "passive"))
    )
    (net (code "134") (name "unconnected-(U1-3A-Pad9)") (class "Default")
      (node (ref "U1") (pin "9") (pinfunction "3A_9") (pintype "passive"))
    )
    (net (code "135") (name "unconnected-(U1-3Y-Pad8)") (class "Default")
      (node (ref "U1") (pin "8") (pinfunction "3Y_8") (pintype "passive"))
    )
    (net (code "136") (name "unconnected-(U1-3nOE-Pad10)") (class "Default")
      (node (ref "U1") (pin "10") (pinfunction "3nOE_10") (pintype "passive"))
    )
    (net (code "137") (name "unconnected-(U1-4A-Pad12)") (class "Default")
      (node (ref "U1") (pin "12") (pinfunction "4A_12") (pintype "passive"))
    )
    (net (code "138") (name "unconnected-(U1-4Y-Pad11)") (class "Default")
      (node (ref "U1") (pin "11") (pinfunction "4Y_11") (pintype "passive"))
    )
    (net (code "139") (name "unconnected-(U1-4nOE-Pad13)") (class "Default")
      (node (ref "U1") (pin "13") (pinfunction "4nOE_13") (pintype "passive"))
    )
    (net (code "140") (name "unconnected-(U2-2A-Pad5)") (class "Default")
      (node (ref "U2") (pin "5") (pinfunction "2A_5") (pintype "passive"))
    )
    (net (code "141") (name "unconnected-(U2-2OE-Pad4)") (class "Default")
      (node (ref "U2") (pin "4") (pinfunction "2OE_4") (pintype "passive"))
    )
    (net (code "142") (name "unconnected-(U2-2Y-Pad6)") (class "Default")
      (node (ref "U2") (pin "6") (pinfunction "2Y_6") (pintype "passive"))
    )
    (net (code "143") (name "unconnected-(U2-3A-Pad9)") (class "Default")
      (node (ref "U2") (pin "9") (pinfunction "3A_9") (pintype "passive"))
    )
    (net (code "144") (name "unconnected-(U2-3OE-Pad10)") (class "Default")
      (node (ref "U2") (pin "10") (pinfunction "3OE_10") (pintype "passive"))
    )
    (net (code "145") (name "unconnected-(U2-3Y-Pad8)") (class "Default")
      (node (ref "U2") (pin "8") (pinfunction "3Y_8") (pintype "passive"))
    )
    (net (code "146") (name "unconnected-(U2-4A-Pad12)") (class "Default")
      (node (ref "U2") (pin "12") (pinfunction "4A_12") (pintype "passive"))
    )
    (net (code "147") (name "unconnected-(U2-4OE-Pad13)") (class "Default")
      (node (ref "U2") (pin "13") (pinfunction "4OE_13") (pintype "passive"))
    )
    (net (code "148") (name "unconnected-(U2-4Y-Pad11)") (class "Default")
      (node (ref "U2") (pin "11") (pinfunction "4Y_11") (pintype "passive"))
    )
    (net (code "149") (name "unconnected-(USB-C1-DN1-PadA7)") (class "Default")
      (node (ref "USB-C1") (pin "A7") (pinfunction "DN1_A7") (pintype "passive"))
    )
    (net (code "150") (name "unconnected-(USB-C1-DN2-PadB7)") (class "Default")
      (node (ref "USB-C1") (pin "B7") (pinfunction "DN2_B7") (pintype "passive"))
    )
    (net (code "151") (name "unconnected-(USB-C1-DP1-PadA6)") (class "Default")
      (node (ref "USB-C1") (pin "A6") (pinfunction "DP1_A6") (pintype "passive"))
    )
    (net (code "152") (name "unconnected-(USB-C1-DP2-PadB6)") (class "Default")
      (node (ref "USB-C1") (pin "B6") (pinfunction "DP2_B6") (pintype "passive"))
    )
    (net (code "153") (name "unconnected-(USB-C1-SBU1-PadA8)") (class "Default")
      (node (ref "USB-C1") (pin "A8") (pinfunction "SBU1_A8") (pintype "passive"))
    )
    (net (code "154") (name "unconnected-(USB-C1-SBU2-PadB8)") (class "Default")
      (node (ref "USB-C1") (pin "B8") (pinfunction "SBU2_B8") (pintype "passive"))
    )
    (net (code "155") (name "unconnected-(USB-C1-SHELL-Pad1)") (class "Default")
      (node (ref "USB-C1") (pin "1") (pinfunction "SHELL_1") (pintype "passive"))
    )
    (net (code "156") (name "unconnected-(USB-C1-SHELL-Pad2)") (class "Default")
      (node (ref "USB-C1") (pin "2") (pinfunction "SHELL_2") (pintype "passive"))
    )
    (net (code "157") (name "unconnected-(USB-C1-SHELL-Pad3)") (class "Default")
      (node (ref "USB-C1") (pin "3") (pinfunction "SHELL_3") (pintype "passive"))
    )
    (net (code "158") (name "unconnected-(USB-C1-SHELL-Pad4)") (class "Default")
      (node (ref "USB-C1") (pin "4") (pinfunction "SHELL_4") (pintype "passive"))
    )
  )
)
